# Power.net
KiCad netlist of a schematic drawn in Altium Designer
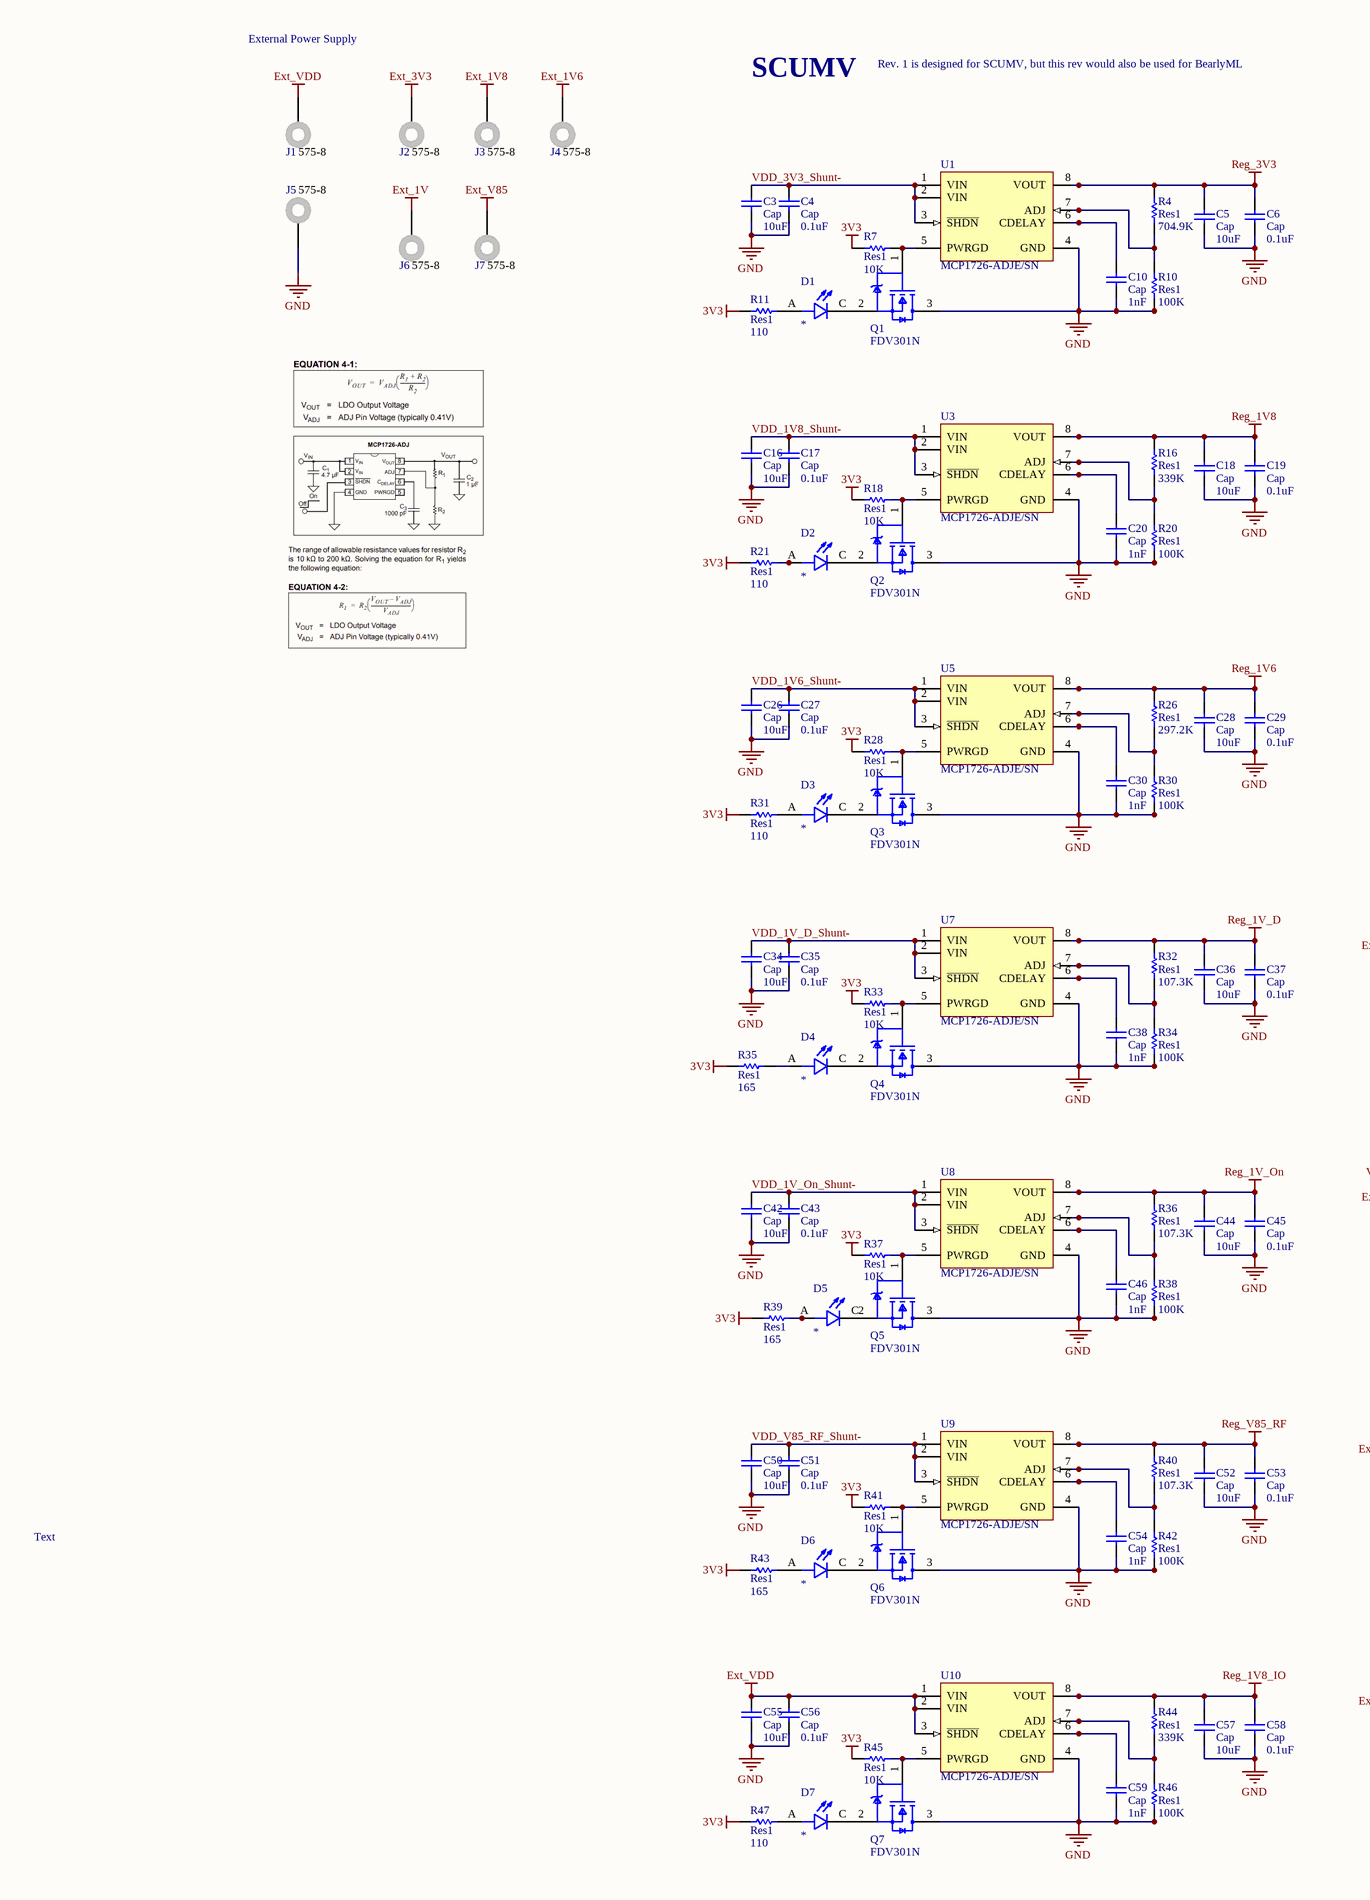
[diagram p0: Power.SchDoc, left]
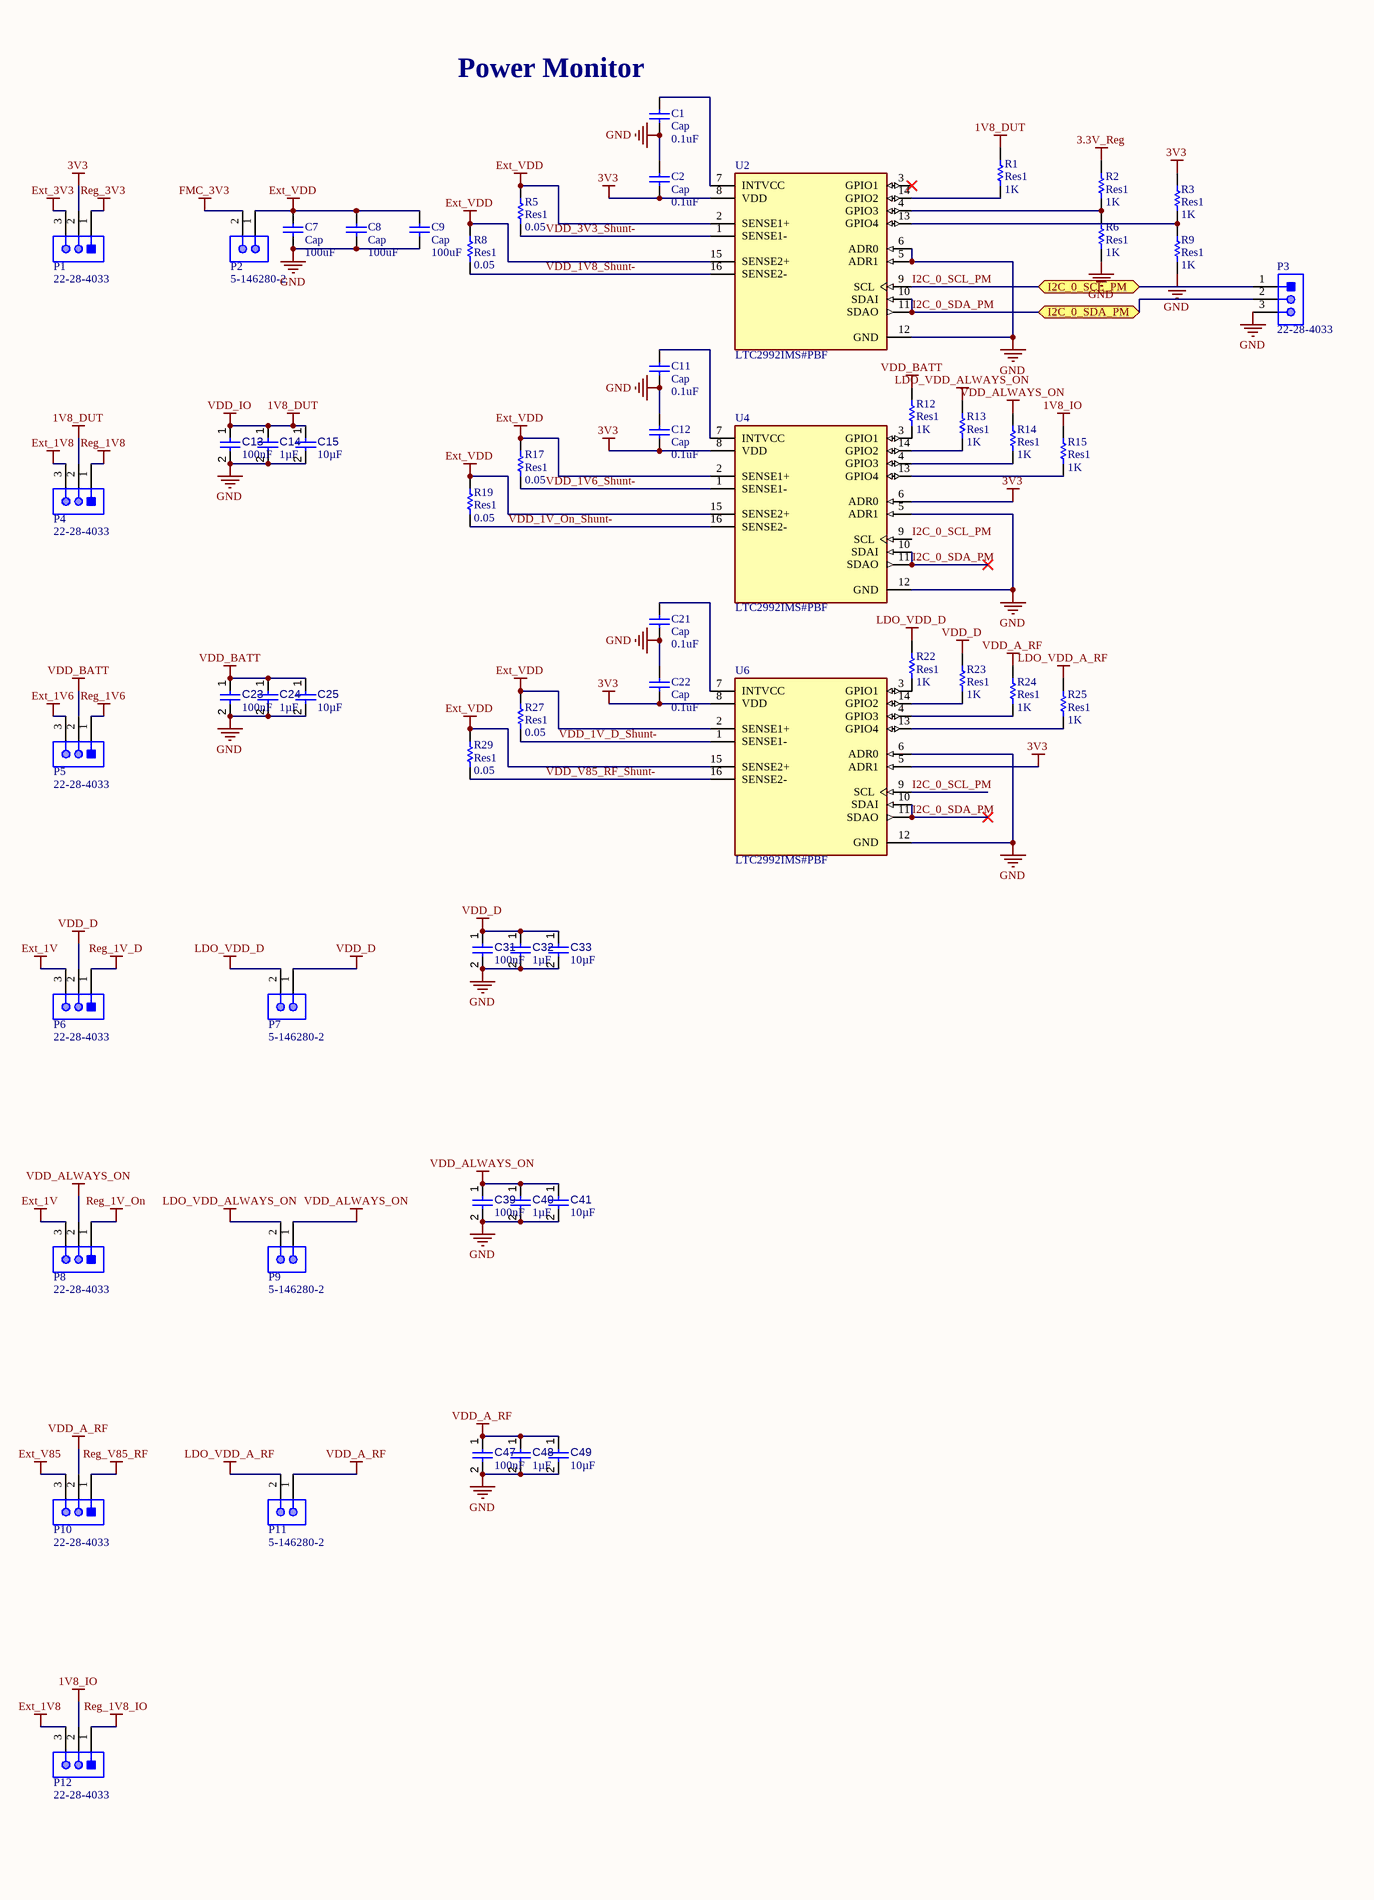
[diagram p1: Power.SchDoc, right]

(export (version "E")
  (design (tool "Eeschema 10.0.6"))
  (components
    (comp (ref "C1")
      (value "Cap")
      (footprint "0603")
      (description "Capacitor")
      (fields (field (name "ALTIUM_VALUE") "0.1uF") (field (name "PUBLISHER") "Altium Limited"))
      (libsource (lib "Miscellaneous Devices") (part "Cap"))
    )
    (comp (ref "C2")
      (value "Cap")
      (footprint "0603")
      (description "Capacitor")
      (fields (field (name "ALTIUM_VALUE") "0.1uF") (field (name "PUBLISHER") "Altium Limited"))
      (libsource (lib "Miscellaneous Devices") (part "Cap"))
    )
    (comp (ref "C3")
      (value "Cap")
      (footprint "0805")
      (description "Capacitor")
      (fields (field (name "ALTIUM_VALUE") "10uF") (field (name "PUBLISHER") "Altium Limited"))
      (libsource (lib "Miscellaneous Devices") (part "Cap"))
    )
    (comp (ref "C4")
      (value "Cap")
      (footprint "0603")
      (description "Capacitor")
      (fields (field (name "ALTIUM_VALUE") "0.1uF") (field (name "PUBLISHER") "Altium Limited"))
      (libsource (lib "Miscellaneous Devices") (part "Cap"))
    )
    (comp (ref "C5")
      (value "Cap")
      (footprint "0805")
      (description "Capacitor")
      (fields (field (name "ALTIUM_VALUE") "10uF") (field (name "PUBLISHER") "Altium Limited"))
      (libsource (lib "Miscellaneous Devices") (part "Cap"))
    )
    (comp (ref "C6")
      (value "Cap")
      (footprint "0603")
      (description "Capacitor")
      (fields (field (name "ALTIUM_VALUE") "0.1uF") (field (name "PUBLISHER") "Altium Limited"))
      (libsource (lib "Miscellaneous Devices") (part "Cap"))
    )
    (comp (ref "C7")
      (value "Cap")
      (footprint "0805")
      (description "Capacitor")
      (fields (field (name "ALTIUM_VALUE") "100uF") (field (name "PUBLISHER") "Altium Limited"))
      (libsource (lib "Miscellaneous Devices") (part "Cap"))
    )
    (comp (ref "C8")
      (value "Cap")
      (footprint "0805")
      (description "Capacitor")
      (fields (field (name "ALTIUM_VALUE") "100uF") (field (name "PUBLISHER") "Altium Limited"))
      (libsource (lib "Miscellaneous Devices") (part "Cap"))
    )
    (comp (ref "C9")
      (value "Cap")
      (footprint "0805")
      (description "Capacitor")
      (fields (field (name "ALTIUM_VALUE") "100uF") (field (name "PUBLISHER") "Altium Limited"))
      (libsource (lib "Miscellaneous Devices") (part "Cap"))
    )
    (comp (ref "C10")
      (value "Cap")
      (footprint "0603")
      (description "Capacitor")
      (fields (field (name "ALTIUM_VALUE") "1nF") (field (name "PUBLISHER") "Altium Limited"))
      (libsource (lib "Miscellaneous Devices") (part "Cap"))
    )
    (comp (ref "C11")
      (value "Cap")
      (footprint "0603")
      (description "Capacitor")
      (fields (field (name "ALTIUM_VALUE") "0.1uF") (field (name "PUBLISHER") "Altium Limited"))
      (libsource (lib "Miscellaneous Devices") (part "Cap"))
    )
    (comp (ref "C12")
      (value "Cap")
      (footprint "0603")
      (description "Capacitor")
      (fields (field (name "ALTIUM_VALUE") "0.1uF") (field (name "PUBLISHER") "Altium Limited"))
      (libsource (lib "Miscellaneous Devices") (part "Cap"))
    )
    (comp (ref "C13")
      (value "100nF")
      (footprint "CAPC0402(1005)60_L")
      (description "Chip Capacitor, 100nF +/-20%, 10V, 0402, Thickness 0.6 mm")
      (fields (field (name "TOLERANCE") "20%") (field (name "Comment") "Capacitor 100nF +/-20% 10V 0402"))
      (libsource (lib "EE194 Fall2022") (part "CAP-NP-2"))
    )
    (comp (ref "C14")
      (value "1µF")
      (footprint "CAPC0402(1005)60_L")
      (description "Chip Capacitor, 1µF +/-20%, 10V, 0402, Thickness 0.6 mm")
      (fields (field (name "TOLERANCE") "10%") (field (name "Comment") "Capacitor 1µF +/-20% 10V 0402"))
      (libsource (lib "EE194 Fall2022") (part "CAP-NP-2"))
    )
    (comp (ref "C15")
      (value "10µF")
      (footprint "CAPC0402(1005)60_L")
      (description "Chip Capacitor, 10µF +/-40%, 6.3V, 0402, Thickness 0.6 mm")
      (fields (field (name "TOLERANCE") "10%") (field (name "Comment") "Capacitor 10µF +/-40% 6.3V 0402"))
      (libsource (lib "EE194 Fall2022") (part "CAP-NP-2"))
    )
    (comp (ref "C16")
      (value "Cap")
      (footprint "0805")
      (description "Capacitor")
      (fields (field (name "ALTIUM_VALUE") "10uF") (field (name "PUBLISHER") "Altium Limited"))
      (libsource (lib "Miscellaneous Devices") (part "Cap"))
    )
    (comp (ref "C17")
      (value "Cap")
      (footprint "0603")
      (description "Capacitor")
      (fields (field (name "ALTIUM_VALUE") "0.1uF") (field (name "PUBLISHER") "Altium Limited"))
      (libsource (lib "Miscellaneous Devices") (part "Cap"))
    )
    (comp (ref "C18")
      (value "Cap")
      (footprint "0805")
      (description "Capacitor")
      (fields (field (name "ALTIUM_VALUE") "10uF") (field (name "PUBLISHER") "Altium Limited"))
      (libsource (lib "Miscellaneous Devices") (part "Cap"))
    )
    (comp (ref "C19")
      (value "Cap")
      (footprint "0603")
      (description "Capacitor")
      (fields (field (name "ALTIUM_VALUE") "0.1uF") (field (name "PUBLISHER") "Altium Limited"))
      (libsource (lib "Miscellaneous Devices") (part "Cap"))
    )
    (comp (ref "C20")
      (value "Cap")
      (footprint "0603")
      (description "Capacitor")
      (fields (field (name "ALTIUM_VALUE") "1nF") (field (name "PUBLISHER") "Altium Limited"))
      (libsource (lib "Miscellaneous Devices") (part "Cap"))
    )
    (comp (ref "C21")
      (value "Cap")
      (footprint "0603")
      (description "Capacitor")
      (fields (field (name "ALTIUM_VALUE") "0.1uF") (field (name "PUBLISHER") "Altium Limited"))
      (libsource (lib "Miscellaneous Devices") (part "Cap"))
    )
    (comp (ref "C22")
      (value "Cap")
      (footprint "0603")
      (description "Capacitor")
      (fields (field (name "ALTIUM_VALUE") "0.1uF") (field (name "PUBLISHER") "Altium Limited"))
      (libsource (lib "Miscellaneous Devices") (part "Cap"))
    )
    (comp (ref "C23")
      (value "100nF")
      (footprint "CAPC0402(1005)60_L")
      (description "Chip Capacitor, 100nF +/-20%, 10V, 0402, Thickness 0.6 mm")
      (fields (field (name "TOLERANCE") "20%") (field (name "Comment") "Capacitor 100nF +/-20% 10V 0402"))
      (libsource (lib "EE194 Fall2022") (part "CAP-NP-2"))
    )
    (comp (ref "C24")
      (value "1µF")
      (footprint "CAPC0402(1005)60_L")
      (description "Chip Capacitor, 1µF +/-20%, 10V, 0402, Thickness 0.6 mm")
      (fields (field (name "TOLERANCE") "10%") (field (name "Comment") "Capacitor 1µF +/-20% 10V 0402"))
      (libsource (lib "EE194 Fall2022") (part "CAP-NP-2"))
    )
    (comp (ref "C25")
      (value "10µF")
      (footprint "CAPC0402(1005)60_L")
      (description "Chip Capacitor, 10µF +/-40%, 6.3V, 0402, Thickness 0.6 mm")
      (fields (field (name "TOLERANCE") "10%") (field (name "Comment") "Capacitor 10µF +/-40% 6.3V 0402"))
      (libsource (lib "EE194 Fall2022") (part "CAP-NP-2"))
    )
    (comp (ref "C26")
      (value "Cap")
      (footprint "0805")
      (description "Capacitor")
      (fields (field (name "ALTIUM_VALUE") "10uF") (field (name "PUBLISHER") "Altium Limited"))
      (libsource (lib "Miscellaneous Devices") (part "Cap"))
    )
    (comp (ref "C27")
      (value "Cap")
      (footprint "0603")
      (description "Capacitor")
      (fields (field (name "ALTIUM_VALUE") "0.1uF") (field (name "PUBLISHER") "Altium Limited"))
      (libsource (lib "Miscellaneous Devices") (part "Cap"))
    )
    (comp (ref "C28")
      (value "Cap")
      (footprint "0805")
      (description "Capacitor")
      (fields (field (name "ALTIUM_VALUE") "10uF") (field (name "PUBLISHER") "Altium Limited"))
      (libsource (lib "Miscellaneous Devices") (part "Cap"))
    )
    (comp (ref "C29")
      (value "Cap")
      (footprint "0603")
      (description "Capacitor")
      (fields (field (name "ALTIUM_VALUE") "0.1uF") (field (name "PUBLISHER") "Altium Limited"))
      (libsource (lib "Miscellaneous Devices") (part "Cap"))
    )
    (comp (ref "C30")
      (value "Cap")
      (footprint "0603")
      (description "Capacitor")
      (fields (field (name "ALTIUM_VALUE") "1nF") (field (name "PUBLISHER") "Altium Limited"))
      (libsource (lib "Miscellaneous Devices") (part "Cap"))
    )
    (comp (ref "C31")
      (value "100nF")
      (footprint "CAPC0402(1005)60_L")
      (description "Chip Capacitor, 100nF +/-20%, 10V, 0402, Thickness 0.6 mm")
      (fields (field (name "TOLERANCE") "20%") (field (name "Comment") "Capacitor 100nF +/-20% 10V 0402"))
      (libsource (lib "EE194 Fall2022") (part "CAP-NP-2"))
    )
    (comp (ref "C32")
      (value "1µF")
      (footprint "CAPC0402(1005)60_L")
      (description "Chip Capacitor, 1µF +/-20%, 10V, 0402, Thickness 0.6 mm")
      (fields (field (name "TOLERANCE") "10%") (field (name "Comment") "Capacitor 1µF +/-20% 10V 0402"))
      (libsource (lib "EE194 Fall2022") (part "CAP-NP-2"))
    )
    (comp (ref "C33")
      (value "10µF")
      (footprint "CAPC0402(1005)60_L")
      (description "Chip Capacitor, 10µF +/-40%, 6.3V, 0402, Thickness 0.6 mm")
      (fields (field (name "TOLERANCE") "10%") (field (name "Comment") "Capacitor 10µF +/-40% 6.3V 0402"))
      (libsource (lib "EE194 Fall2022") (part "CAP-NP-2"))
    )
    (comp (ref "C34")
      (value "Cap")
      (footprint "0805")
      (description "Capacitor")
      (fields (field (name "ALTIUM_VALUE") "10uF") (field (name "PUBLISHER") "Altium Limited"))
      (libsource (lib "Miscellaneous Devices") (part "Cap"))
    )
    (comp (ref "C35")
      (value "Cap")
      (footprint "0603")
      (description "Capacitor")
      (fields (field (name "ALTIUM_VALUE") "0.1uF") (field (name "PUBLISHER") "Altium Limited"))
      (libsource (lib "Miscellaneous Devices") (part "Cap"))
    )
    (comp (ref "C36")
      (value "Cap")
      (footprint "0805")
      (description "Capacitor")
      (fields (field (name "ALTIUM_VALUE") "10uF") (field (name "PUBLISHER") "Altium Limited"))
      (libsource (lib "Miscellaneous Devices") (part "Cap"))
    )
    (comp (ref "C37")
      (value "Cap")
      (footprint "0603")
      (description "Capacitor")
      (fields (field (name "ALTIUM_VALUE") "0.1uF") (field (name "PUBLISHER") "Altium Limited"))
      (libsource (lib "Miscellaneous Devices") (part "Cap"))
    )
    (comp (ref "C38")
      (value "Cap")
      (footprint "0603")
      (description "Capacitor")
      (fields (field (name "ALTIUM_VALUE") "1nF") (field (name "PUBLISHER") "Altium Limited"))
      (libsource (lib "Miscellaneous Devices") (part "Cap"))
    )
    (comp (ref "C39")
      (value "100nF")
      (footprint "CAPC0402(1005)60_L")
      (description "Chip Capacitor, 100nF +/-20%, 10V, 0402, Thickness 0.6 mm")
      (fields (field (name "TOLERANCE") "20%") (field (name "Comment") "Capacitor 100nF +/-20% 10V 0402"))
      (libsource (lib "EE194 Fall2022") (part "CAP-NP-2"))
    )
    (comp (ref "C40")
      (value "1µF")
      (footprint "CAPC0402(1005)60_L")
      (description "Chip Capacitor, 1µF +/-20%, 10V, 0402, Thickness 0.6 mm")
      (fields (field (name "TOLERANCE") "10%") (field (name "Comment") "Capacitor 1µF +/-20% 10V 0402"))
      (libsource (lib "EE194 Fall2022") (part "CAP-NP-2"))
    )
    (comp (ref "C41")
      (value "10µF")
      (footprint "CAPC0402(1005)60_L")
      (description "Chip Capacitor, 10µF +/-40%, 6.3V, 0402, Thickness 0.6 mm")
      (fields (field (name "TOLERANCE") "10%") (field (name "Comment") "Capacitor 10µF +/-40% 6.3V 0402"))
      (libsource (lib "EE194 Fall2022") (part "CAP-NP-2"))
    )
    (comp (ref "C42")
      (value "Cap")
      (footprint "0805")
      (description "Capacitor")
      (fields (field (name "ALTIUM_VALUE") "10uF") (field (name "PUBLISHER") "Altium Limited"))
      (libsource (lib "Miscellaneous Devices") (part "Cap"))
    )
    (comp (ref "C43")
      (value "Cap")
      (footprint "0603")
      (description "Capacitor")
      (fields (field (name "ALTIUM_VALUE") "0.1uF") (field (name "PUBLISHER") "Altium Limited"))
      (libsource (lib "Miscellaneous Devices") (part "Cap"))
    )
    (comp (ref "C44")
      (value "Cap")
      (footprint "0805")
      (description "Capacitor")
      (fields (field (name "ALTIUM_VALUE") "10uF") (field (name "PUBLISHER") "Altium Limited"))
      (libsource (lib "Miscellaneous Devices") (part "Cap"))
    )
    (comp (ref "C45")
      (value "Cap")
      (footprint "0603")
      (description "Capacitor")
      (fields (field (name "ALTIUM_VALUE") "0.1uF") (field (name "PUBLISHER") "Altium Limited"))
      (libsource (lib "Miscellaneous Devices") (part "Cap"))
    )
    (comp (ref "C46")
      (value "Cap")
      (footprint "0603")
      (description "Capacitor")
      (fields (field (name "ALTIUM_VALUE") "1nF") (field (name "PUBLISHER") "Altium Limited"))
      (libsource (lib "Miscellaneous Devices") (part "Cap"))
    )
    (comp (ref "C47")
      (value "100nF")
      (footprint "CAPC0402(1005)60_L")
      (description "Chip Capacitor, 100nF +/-20%, 10V, 0402, Thickness 0.6 mm")
      (fields (field (name "TOLERANCE") "20%") (field (name "Comment") "Capacitor 100nF +/-20% 10V 0402"))
      (libsource (lib "EE194 Fall2022") (part "CAP-NP-2"))
    )
    (comp (ref "C48")
      (value "1µF")
      (footprint "CAPC0402(1005)60_L")
      (description "Chip Capacitor, 1µF +/-20%, 10V, 0402, Thickness 0.6 mm")
      (fields (field (name "TOLERANCE") "10%") (field (name "Comment") "Capacitor 1µF +/-20% 10V 0402"))
      (libsource (lib "EE194 Fall2022") (part "CAP-NP-2"))
    )
    (comp (ref "C49")
      (value "10µF")
      (footprint "CAPC0402(1005)60_L")
      (description "Chip Capacitor, 10µF +/-40%, 6.3V, 0402, Thickness 0.6 mm")
      (fields (field (name "TOLERANCE") "10%") (field (name "Comment") "Capacitor 10µF +/-40% 6.3V 0402"))
      (libsource (lib "EE194 Fall2022") (part "CAP-NP-2"))
    )
    (comp (ref "C50")
      (value "Cap")
      (footprint "0805")
      (description "Capacitor")
      (fields (field (name "ALTIUM_VALUE") "10uF") (field (name "PUBLISHER") "Altium Limited"))
      (libsource (lib "Miscellaneous Devices") (part "Cap"))
    )
    (comp (ref "C51")
      (value "Cap")
      (footprint "0603")
      (description "Capacitor")
      (fields (field (name "ALTIUM_VALUE") "0.1uF") (field (name "PUBLISHER") "Altium Limited"))
      (libsource (lib "Miscellaneous Devices") (part "Cap"))
    )
    (comp (ref "C52")
      (value "Cap")
      (footprint "0805")
      (description "Capacitor")
      (fields (field (name "ALTIUM_VALUE") "10uF") (field (name "PUBLISHER") "Altium Limited"))
      (libsource (lib "Miscellaneous Devices") (part "Cap"))
    )
    (comp (ref "C53")
      (value "Cap")
      (footprint "0603")
      (description "Capacitor")
      (fields (field (name "ALTIUM_VALUE") "0.1uF") (field (name "PUBLISHER") "Altium Limited"))
      (libsource (lib "Miscellaneous Devices") (part "Cap"))
    )
    (comp (ref "C54")
      (value "Cap")
      (footprint "0603")
      (description "Capacitor")
      (fields (field (name "ALTIUM_VALUE") "1nF") (field (name "PUBLISHER") "Altium Limited"))
      (libsource (lib "Miscellaneous Devices") (part "Cap"))
    )
    (comp (ref "C55")
      (value "Cap")
      (footprint "0805")
      (description "Capacitor")
      (fields (field (name "ALTIUM_VALUE") "10uF") (field (name "PUBLISHER") "Altium Limited"))
      (libsource (lib "Miscellaneous Devices") (part "Cap"))
    )
    (comp (ref "C56")
      (value "Cap")
      (footprint "0603")
      (description "Capacitor")
      (fields (field (name "ALTIUM_VALUE") "0.1uF") (field (name "PUBLISHER") "Altium Limited"))
      (libsource (lib "Miscellaneous Devices") (part "Cap"))
    )
    (comp (ref "C57")
      (value "Cap")
      (footprint "0805")
      (description "Capacitor")
      (fields (field (name "ALTIUM_VALUE") "10uF") (field (name "PUBLISHER") "Altium Limited"))
      (libsource (lib "Miscellaneous Devices") (part "Cap"))
    )
    (comp (ref "C58")
      (value "Cap")
      (footprint "0603")
      (description "Capacitor")
      (fields (field (name "ALTIUM_VALUE") "0.1uF") (field (name "PUBLISHER") "Altium Limited"))
      (libsource (lib "Miscellaneous Devices") (part "Cap"))
    )
    (comp (ref "C59")
      (value "Cap")
      (footprint "0603")
      (description "Capacitor")
      (fields (field (name "ALTIUM_VALUE") "1nF") (field (name "PUBLISHER") "Altium Limited"))
      (libsource (lib "Miscellaneous Devices") (part "Cap"))
    )
    (comp (ref "D1")
      (value "LTW-C191DS5")
      (footprint "LED0603")
      (description "White LED Indication - Discrete 2.93V 0603 _1608 Metric_")
      (fields (field (name "MF") "Lite-On Inc.") (field (name "ALTIUM_VALUE") "*"))
      (libsource (lib "EE194 Fall2022") (part "LTW-C191DS5"))
    )
    (comp (ref "D2")
      (value "LTW-C191DS5")
      (footprint "LED0603")
      (description "White LED Indication - Discrete 2.93V 0603 _1608 Metric_")
      (fields (field (name "MF") "Lite-On Inc.") (field (name "ALTIUM_VALUE") "*"))
      (libsource (lib "EE194 Fall2022") (part "LTW-C191DS5"))
    )
    (comp (ref "D3")
      (value "LTW-C191DS5")
      (footprint "LED0603")
      (description "White LED Indication - Discrete 2.93V 0603 _1608 Metric_")
      (fields (field (name "MF") "Lite-On Inc.") (field (name "ALTIUM_VALUE") "*"))
      (libsource (lib "EE194 Fall2022") (part "LTW-C191DS5"))
    )
    (comp (ref "D4")
      (value "LTW-C191DS5")
      (footprint "LED0603")
      (description "White LED Indication - Discrete 2.93V 0603 _1608 Metric_")
      (fields (field (name "MF") "Lite-On Inc.") (field (name "ALTIUM_VALUE") "*"))
      (libsource (lib "EE194 Fall2022") (part "LTW-C191DS5"))
    )
    (comp (ref "D5")
      (value "LTW-C191DS5")
      (footprint "LED0603")
      (description "White LED Indication - Discrete 2.93V 0603 _1608 Metric_")
      (fields (field (name "MF") "Lite-On Inc.") (field (name "ALTIUM_VALUE") "*"))
      (libsource (lib "EE194 Fall2022") (part "LTW-C191DS5"))
    )
    (comp (ref "D6")
      (value "LTW-C191DS5")
      (footprint "LED0603")
      (description "White LED Indication - Discrete 2.93V 0603 _1608 Metric_")
      (fields (field (name "MF") "Lite-On Inc.") (field (name "ALTIUM_VALUE") "*"))
      (libsource (lib "EE194 Fall2022") (part "LTW-C191DS5"))
    )
    (comp (ref "D7")
      (value "LTW-C191DS5")
      (footprint "LED0603")
      (description "White LED Indication - Discrete 2.93V 0603 _1608 Metric_")
      (fields (field (name "MF") "Lite-On Inc.") (field (name "ALTIUM_VALUE") "*"))
      (libsource (lib "EE194 Fall2022") (part "LTW-C191DS5"))
    )
    (comp (ref "J1")
      (value "575-8")
      (footprint "KSTN-575-8")
      (description "Non-Insulated Jack, Through Hole, RoHS, Bulk")
      (fields (field (name "MANUFACTURER") "Keystone"))
      (libsource (lib "Altium Content Vault") (part "KSTN-575-8"))
    )
    (comp (ref "J2")
      (value "575-8")
      (footprint "KSTN-575-8")
      (description "Non-Insulated Jack, Through Hole, RoHS, Bulk")
      (fields (field (name "MANUFACTURER") "Keystone"))
      (libsource (lib "Altium Content Vault") (part "KSTN-575-8"))
    )
    (comp (ref "J3")
      (value "575-8")
      (footprint "KSTN-575-8")
      (description "Non-Insulated Jack, Through Hole, RoHS, Bulk")
      (fields (field (name "MANUFACTURER") "Keystone"))
      (libsource (lib "Altium Content Vault") (part "KSTN-575-8"))
    )
    (comp (ref "J4")
      (value "575-8")
      (footprint "KSTN-575-8")
      (description "Non-Insulated Jack, Through Hole, RoHS, Bulk")
      (fields (field (name "MANUFACTURER") "Keystone"))
      (libsource (lib "Altium Content Vault") (part "KSTN-575-8"))
    )
    (comp (ref "J5")
      (value "575-8")
      (footprint "KSTN-575-8")
      (description "Non-Insulated Jack, Through Hole, RoHS, Bulk")
      (fields (field (name "MANUFACTURER") "Keystone"))
      (libsource (lib "Altium Content Vault") (part "KSTN-575-8"))
    )
    (comp (ref "J6")
      (value "575-8")
      (footprint "KSTN-575-8")
      (description "Non-Insulated Jack, Through Hole, RoHS, Bulk")
      (fields (field (name "MANUFACTURER") "Keystone"))
      (libsource (lib "Altium Content Vault") (part "KSTN-575-8"))
    )
    (comp (ref "J7")
      (value "575-8")
      (footprint "KSTN-575-8")
      (description "Non-Insulated Jack, Through Hole, RoHS, Bulk")
      (fields (field (name "MANUFACTURER") "Keystone"))
      (libsource (lib "Altium Content Vault") (part "KSTN-575-8"))
    )
    (comp (ref "P1")
      (value "22-28-4033")
      (footprint "MOLX-22-28-4033_V")
      (description "Male Header, Pitch 2.54 mm, 1 x 3 Position, Height 8.38 mm, Tail Length 3.18 mm, RoHS, Bulk")
      (fields (field (name "MANUFACTURER") "Molex"))
      (libsource (lib "Altium Content Vault") (part "CN-1P-M-R3"))
    )
    (comp (ref "P2")
      (value "5-146280-2")
      (footprint "TECO-5-146280-2_V")
      (fields (field (name "MANUFACTURER") "TE Connectivity"))
      (libsource (lib "Altium Content Vault") (part "CN-1P-M-R2"))
    )
    (comp (ref "P3")
      (value "22-28-4033")
      (footprint "MOLX-22-28-4033_V")
      (description "Male Header, Pitch 2.54 mm, 1 x 3 Position, Height 8.38 mm, Tail Length 3.18 mm, RoHS, Bulk")
      (fields (field (name "MANUFACTURER") "Molex"))
      (libsource (lib "") (part "CN-1P-M-R3_1"))
    )
    (comp (ref "P4")
      (value "22-28-4033")
      (footprint "MOLX-22-28-4033_V")
      (description "Male Header, Pitch 2.54 mm, 1 x 3 Position, Height 8.38 mm, Tail Length 3.18 mm, RoHS, Bulk")
      (fields (field (name "MANUFACTURER") "Molex"))
      (libsource (lib "Altium Content Vault") (part "CN-1P-M-R3"))
    )
    (comp (ref "P5")
      (value "22-28-4033")
      (footprint "MOLX-22-28-4033_V")
      (description "Male Header, Pitch 2.54 mm, 1 x 3 Position, Height 8.38 mm, Tail Length 3.18 mm, RoHS, Bulk")
      (fields (field (name "MANUFACTURER") "Molex"))
      (libsource (lib "Altium Content Vault") (part "CN-1P-M-R3"))
    )
    (comp (ref "P6")
      (value "22-28-4033")
      (footprint "MOLX-22-28-4033_V")
      (description "Male Header, Pitch 2.54 mm, 1 x 3 Position, Height 8.38 mm, Tail Length 3.18 mm, RoHS, Bulk")
      (fields (field (name "MANUFACTURER") "Molex"))
      (libsource (lib "Altium Content Vault") (part "CN-1P-M-R3"))
    )
    (comp (ref "P7")
      (value "5-146280-2")
      (footprint "TECO-5-146280-2_V")
      (fields (field (name "MANUFACTURER") "TE Connectivity"))
      (libsource (lib "Altium Content Vault") (part "CN-1P-M-R2"))
    )
    (comp (ref "P8")
      (value "22-28-4033")
      (footprint "MOLX-22-28-4033_V")
      (description "Male Header, Pitch 2.54 mm, 1 x 3 Position, Height 8.38 mm, Tail Length 3.18 mm, RoHS, Bulk")
      (fields (field (name "MANUFACTURER") "Molex"))
      (libsource (lib "Altium Content Vault") (part "CN-1P-M-R3"))
    )
    (comp (ref "P9")
      (value "5-146280-2")
      (footprint "TECO-5-146280-2_V")
      (fields (field (name "MANUFACTURER") "TE Connectivity"))
      (libsource (lib "Altium Content Vault") (part "CN-1P-M-R2"))
    )
    (comp (ref "P10")
      (value "22-28-4033")
      (footprint "MOLX-22-28-4033_V")
      (description "Male Header, Pitch 2.54 mm, 1 x 3 Position, Height 8.38 mm, Tail Length 3.18 mm, RoHS, Bulk")
      (fields (field (name "MANUFACTURER") "Molex"))
      (libsource (lib "Altium Content Vault") (part "CN-1P-M-R3"))
    )
    (comp (ref "P11")
      (value "5-146280-2")
      (footprint "TECO-5-146280-2_V")
      (fields (field (name "MANUFACTURER") "TE Connectivity"))
      (libsource (lib "Altium Content Vault") (part "CN-1P-M-R2"))
    )
    (comp (ref "P12")
      (value "22-28-4033")
      (footprint "MOLX-22-28-4033_V")
      (description "Male Header, Pitch 2.54 mm, 1 x 3 Position, Height 8.38 mm, Tail Length 3.18 mm, RoHS, Bulk")
      (fields (field (name "MANUFACTURER") "Molex"))
      (libsource (lib "Altium Content Vault") (part "CN-1P-M-R3"))
    )
    (comp (ref "Q1")
      (value "FDV301N")
      (footprint "FP-318-08-MFG")
      (description "MOSFET N-CH 25V 220MA SOT-23")
      (fields
        (field (name "MANUFACTURER") "ON Semiconductor")
        (field (name "OCTOPART") "https://octopart.com/fdv301n-on+semiconductor-84326713")
      )
      (libsource (lib "Altium Content Vault") (part "4b65c62267dd4506eaef0021093ec31"))
    )
    (comp (ref "Q2")
      (value "FDV301N")
      (footprint "FP-318-08-MFG")
      (description "MOSFET N-CH 25V 220MA SOT-23")
      (fields
        (field (name "MANUFACTURER") "ON Semiconductor")
        (field (name "OCTOPART") "https://octopart.com/fdv301n-on+semiconductor-84326713")
      )
      (libsource (lib "Altium Content Vault") (part "4b65c62267dd4506eaef0021093ec31"))
    )
    (comp (ref "Q3")
      (value "FDV301N")
      (footprint "FP-318-08-MFG")
      (description "MOSFET N-CH 25V 220MA SOT-23")
      (fields
        (field (name "MANUFACTURER") "ON Semiconductor")
        (field (name "OCTOPART") "https://octopart.com/fdv301n-on+semiconductor-84326713")
      )
      (libsource (lib "Altium Content Vault") (part "4b65c62267dd4506eaef0021093ec31"))
    )
    (comp (ref "Q4")
      (value "FDV301N")
      (footprint "FP-318-08-MFG")
      (description "MOSFET N-CH 25V 220MA SOT-23")
      (fields
        (field (name "MANUFACTURER") "ON Semiconductor")
        (field (name "OCTOPART") "https://octopart.com/fdv301n-on+semiconductor-84326713")
      )
      (libsource (lib "Altium Content Vault") (part "4b65c62267dd4506eaef0021093ec31"))
    )
    (comp (ref "Q5")
      (value "FDV301N")
      (footprint "FP-318-08-MFG")
      (description "MOSFET N-CH 25V 220MA SOT-23")
      (fields
        (field (name "MANUFACTURER") "ON Semiconductor")
        (field (name "OCTOPART") "https://octopart.com/fdv301n-on+semiconductor-84326713")
      )
      (libsource (lib "Altium Content Vault") (part "4b65c62267dd4506eaef0021093ec31"))
    )
    (comp (ref "Q6")
      (value "FDV301N")
      (footprint "FP-318-08-MFG")
      (description "MOSFET N-CH 25V 220MA SOT-23")
      (fields
        (field (name "MANUFACTURER") "ON Semiconductor")
        (field (name "OCTOPART") "https://octopart.com/fdv301n-on+semiconductor-84326713")
      )
      (libsource (lib "Altium Content Vault") (part "4b65c62267dd4506eaef0021093ec31"))
    )
    (comp (ref "Q7")
      (value "FDV301N")
      (footprint "FP-318-08-MFG")
      (description "MOSFET N-CH 25V 220MA SOT-23")
      (fields
        (field (name "MANUFACTURER") "ON Semiconductor")
        (field (name "OCTOPART") "https://octopart.com/fdv301n-on+semiconductor-84326713")
      )
      (libsource (lib "Altium Content Vault") (part "4b65c62267dd4506eaef0021093ec31"))
    )
    (comp (ref "R1")
      (value "Res1")
      (footprint "0603")
      (description "Resistor")
      (fields (field (name "ALTIUM_VALUE") "1K") (field (name "PUBLISHER") "Altium Limited"))
      (libsource (lib "Miscellaneous Devices") (part "Res1"))
    )
    (comp (ref "R2")
      (value "Res1")
      (footprint "0603")
      (description "Resistor")
      (fields (field (name "ALTIUM_VALUE") "1K") (field (name "PUBLISHER") "Altium Limited"))
      (libsource (lib "Miscellaneous Devices") (part "Res1"))
    )
    (comp (ref "R3")
      (value "Res1")
      (footprint "0603")
      (description "Resistor")
      (fields (field (name "ALTIUM_VALUE") "1K") (field (name "PUBLISHER") "Altium Limited"))
      (libsource (lib "Miscellaneous Devices") (part "Res1"))
    )
    (comp (ref "R4")
      (value "Res1")
      (footprint "0603")
      (description "Resistor")
      (fields (field (name "ALTIUM_VALUE") "704.9K") (field (name "PUBLISHER") "Altium Limited"))
      (libsource (lib "Miscellaneous Devices") (part "Res1"))
    )
    (comp (ref "R5")
      (value "Res1")
      (footprint "0603")
      (description "Resistor")
      (fields (field (name "ALTIUM_VALUE") "0.05") (field (name "PUBLISHER") "Altium Limited"))
      (libsource (lib "Miscellaneous Devices") (part "Res1"))
    )
    (comp (ref "R6")
      (value "Res1")
      (footprint "0603")
      (description "Resistor")
      (fields (field (name "ALTIUM_VALUE") "1K") (field (name "PUBLISHER") "Altium Limited"))
      (libsource (lib "Miscellaneous Devices") (part "Res1"))
    )
    (comp (ref "R7")
      (value "Res1")
      (footprint "0603")
      (description "Resistor")
      (fields (field (name "ALTIUM_VALUE") "10K") (field (name "PUBLISHER") "Altium Limited"))
      (libsource (lib "Miscellaneous Devices") (part "Res1"))
    )
    (comp (ref "R8")
      (value "Res1")
      (footprint "0603")
      (description "Resistor")
      (fields (field (name "ALTIUM_VALUE") "0.05") (field (name "PUBLISHER") "Altium Limited"))
      (libsource (lib "Miscellaneous Devices") (part "Res1"))
    )
    (comp (ref "R9")
      (value "Res1")
      (footprint "0603")
      (description "Resistor")
      (fields (field (name "ALTIUM_VALUE") "1K") (field (name "PUBLISHER") "Altium Limited"))
      (libsource (lib "Miscellaneous Devices") (part "Res1"))
    )
    (comp (ref "R10")
      (value "Res1")
      (footprint "0603")
      (description "Resistor")
      (fields (field (name "ALTIUM_VALUE") "100K") (field (name "PUBLISHER") "Altium Limited"))
      (libsource (lib "Miscellaneous Devices") (part "Res1"))
    )
    (comp (ref "R11")
      (value "Res1")
      (footprint "0603")
      (description "Resistor")
      (fields (field (name "ALTIUM_VALUE") "110") (field (name "PUBLISHER") "Altium Limited"))
      (libsource (lib "Miscellaneous Devices") (part "Res1"))
    )
    (comp (ref "R12")
      (value "Res1")
      (footprint "0603")
      (description "Resistor")
      (fields (field (name "ALTIUM_VALUE") "1K") (field (name "PUBLISHER") "Altium Limited"))
      (libsource (lib "Miscellaneous Devices") (part "Res1"))
    )
    (comp (ref "R13")
      (value "Res1")
      (footprint "0603")
      (description "Resistor")
      (fields (field (name "ALTIUM_VALUE") "1K") (field (name "PUBLISHER") "Altium Limited"))
      (libsource (lib "Miscellaneous Devices") (part "Res1"))
    )
    (comp (ref "R14")
      (value "Res1")
      (footprint "0603")
      (description "Resistor")
      (fields (field (name "ALTIUM_VALUE") "1K") (field (name "PUBLISHER") "Altium Limited"))
      (libsource (lib "Miscellaneous Devices") (part "Res1"))
    )
    (comp (ref "R15")
      (value "Res1")
      (footprint "0603")
      (description "Resistor")
      (fields (field (name "ALTIUM_VALUE") "1K") (field (name "PUBLISHER") "Altium Limited"))
      (libsource (lib "Miscellaneous Devices") (part "Res1"))
    )
    (comp (ref "R16")
      (value "Res1")
      (footprint "0603")
      (description "Resistor")
      (fields (field (name "ALTIUM_VALUE") "339K") (field (name "PUBLISHER") "Altium Limited"))
      (libsource (lib "Miscellaneous Devices") (part "Res1"))
    )
    (comp (ref "R17")
      (value "Res1")
      (footprint "0603")
      (description "Resistor")
      (fields (field (name "ALTIUM_VALUE") "0.05") (field (name "PUBLISHER") "Altium Limited"))
      (libsource (lib "Miscellaneous Devices") (part "Res1"))
    )
    (comp (ref "R18")
      (value "Res1")
      (footprint "0603")
      (description "Resistor")
      (fields (field (name "ALTIUM_VALUE") "10K") (field (name "PUBLISHER") "Altium Limited"))
      (libsource (lib "Miscellaneous Devices") (part "Res1"))
    )
    (comp (ref "R19")
      (value "Res1")
      (footprint "0603")
      (description "Resistor")
      (fields (field (name "ALTIUM_VALUE") "0.05") (field (name "PUBLISHER") "Altium Limited"))
      (libsource (lib "Miscellaneous Devices") (part "Res1"))
    )
    (comp (ref "R20")
      (value "Res1")
      (footprint "0603")
      (description "Resistor")
      (fields (field (name "ALTIUM_VALUE") "100K") (field (name "PUBLISHER") "Altium Limited"))
      (libsource (lib "Miscellaneous Devices") (part "Res1"))
    )
    (comp (ref "R21")
      (value "Res1")
      (footprint "0603")
      (description "Resistor")
      (fields (field (name "ALTIUM_VALUE") "110") (field (name "PUBLISHER") "Altium Limited"))
      (libsource (lib "Miscellaneous Devices") (part "Res1"))
    )
    (comp (ref "R22")
      (value "Res1")
      (footprint "0603")
      (description "Resistor")
      (fields (field (name "ALTIUM_VALUE") "1K") (field (name "PUBLISHER") "Altium Limited"))
      (libsource (lib "Miscellaneous Devices") (part "Res1"))
    )
    (comp (ref "R23")
      (value "Res1")
      (footprint "0603")
      (description "Resistor")
      (fields (field (name "ALTIUM_VALUE") "1K") (field (name "PUBLISHER") "Altium Limited"))
      (libsource (lib "Miscellaneous Devices") (part "Res1"))
    )
    (comp (ref "R24")
      (value "Res1")
      (footprint "0603")
      (description "Resistor")
      (fields (field (name "ALTIUM_VALUE") "1K") (field (name "PUBLISHER") "Altium Limited"))
      (libsource (lib "Miscellaneous Devices") (part "Res1"))
    )
    (comp (ref "R25")
      (value "Res1")
      (footprint "0603")
      (description "Resistor")
      (fields (field (name "ALTIUM_VALUE") "1K") (field (name "PUBLISHER") "Altium Limited"))
      (libsource (lib "Miscellaneous Devices") (part "Res1"))
    )
    (comp (ref "R26")
      (value "Res1")
      (footprint "0603")
      (description "Resistor")
      (fields (field (name "ALTIUM_VALUE") "297.2K") (field (name "PUBLISHER") "Altium Limited"))
      (libsource (lib "Miscellaneous Devices") (part "Res1"))
    )
    (comp (ref "R27")
      (value "Res1")
      (footprint "0603")
      (description "Resistor")
      (fields (field (name "ALTIUM_VALUE") "0.05") (field (name "PUBLISHER") "Altium Limited"))
      (libsource (lib "Miscellaneous Devices") (part "Res1"))
    )
    (comp (ref "R28")
      (value "Res1")
      (footprint "0603")
      (description "Resistor")
      (fields (field (name "ALTIUM_VALUE") "10K") (field (name "PUBLISHER") "Altium Limited"))
      (libsource (lib "Miscellaneous Devices") (part "Res1"))
    )
    (comp (ref "R29")
      (value "Res1")
      (footprint "0603")
      (description "Resistor")
      (fields (field (name "ALTIUM_VALUE") "0.05") (field (name "PUBLISHER") "Altium Limited"))
      (libsource (lib "Miscellaneous Devices") (part "Res1"))
    )
    (comp (ref "R30")
      (value "Res1")
      (footprint "0603")
      (description "Resistor")
      (fields (field (name "ALTIUM_VALUE") "100K") (field (name "PUBLISHER") "Altium Limited"))
      (libsource (lib "Miscellaneous Devices") (part "Res1"))
    )
    (comp (ref "R31")
      (value "Res1")
      (footprint "0603")
      (description "Resistor")
      (fields (field (name "ALTIUM_VALUE") "110") (field (name "PUBLISHER") "Altium Limited"))
      (libsource (lib "Miscellaneous Devices") (part "Res1"))
    )
    (comp (ref "R32")
      (value "Res1")
      (footprint "0603")
      (description "Resistor")
      (fields (field (name "ALTIUM_VALUE") "107.3K") (field (name "PUBLISHER") "Altium Limited"))
      (libsource (lib "Miscellaneous Devices") (part "Res1"))
    )
    (comp (ref "R33")
      (value "Res1")
      (footprint "0603")
      (description "Resistor")
      (fields (field (name "ALTIUM_VALUE") "10K") (field (name "PUBLISHER") "Altium Limited"))
      (libsource (lib "Miscellaneous Devices") (part "Res1"))
    )
    (comp (ref "R34")
      (value "Res1")
      (footprint "0603")
      (description "Resistor")
      (fields (field (name "ALTIUM_VALUE") "100K") (field (name "PUBLISHER") "Altium Limited"))
      (libsource (lib "Miscellaneous Devices") (part "Res1"))
    )
    (comp (ref "R35")
      (value "Res1")
      (footprint "0603")
      (description "Resistor")
      (fields (field (name "ALTIUM_VALUE") "165") (field (name "PUBLISHER") "Altium Limited"))
      (libsource (lib "Miscellaneous Devices") (part "Res1"))
    )
    (comp (ref "R36")
      (value "Res1")
      (footprint "0603")
      (description "Resistor")
      (fields (field (name "ALTIUM_VALUE") "107.3K") (field (name "PUBLISHER") "Altium Limited"))
      (libsource (lib "Miscellaneous Devices") (part "Res1"))
    )
    (comp (ref "R37")
      (value "Res1")
      (footprint "0603")
      (description "Resistor")
      (fields (field (name "ALTIUM_VALUE") "10K") (field (name "PUBLISHER") "Altium Limited"))
      (libsource (lib "Miscellaneous Devices") (part "Res1"))
    )
    (comp (ref "R38")
      (value "Res1")
      (footprint "0603")
      (description "Resistor")
      (fields (field (name "ALTIUM_VALUE") "100K") (field (name "PUBLISHER") "Altium Limited"))
      (libsource (lib "Miscellaneous Devices") (part "Res1"))
    )
    (comp (ref "R39")
      (value "Res1")
      (footprint "0603")
      (description "Resistor")
      (fields (field (name "ALTIUM_VALUE") "165") (field (name "PUBLISHER") "Altium Limited"))
      (libsource (lib "Miscellaneous Devices") (part "Res1"))
    )
    (comp (ref "R40")
      (value "Res1")
      (footprint "0603")
      (description "Resistor")
      (fields (field (name "ALTIUM_VALUE") "107.3K") (field (name "PUBLISHER") "Altium Limited"))
      (libsource (lib "Miscellaneous Devices") (part "Res1"))
    )
    (comp (ref "R41")
      (value "Res1")
      (footprint "0603")
      (description "Resistor")
      (fields (field (name "ALTIUM_VALUE") "10K") (field (name "PUBLISHER") "Altium Limited"))
      (libsource (lib "Miscellaneous Devices") (part "Res1"))
    )
    (comp (ref "R42")
      (value "Res1")
      (footprint "0603")
      (description "Resistor")
      (fields (field (name "ALTIUM_VALUE") "100K") (field (name "PUBLISHER") "Altium Limited"))
      (libsource (lib "Miscellaneous Devices") (part "Res1"))
    )
    (comp (ref "R43")
      (value "Res1")
      (footprint "0603")
      (description "Resistor")
      (fields (field (name "ALTIUM_VALUE") "165") (field (name "PUBLISHER") "Altium Limited"))
      (libsource (lib "Miscellaneous Devices") (part "Res1"))
    )
    (comp (ref "R44")
      (value "Res1")
      (footprint "0603")
      (description "Resistor")
      (fields (field (name "ALTIUM_VALUE") "339K") (field (name "PUBLISHER") "Altium Limited"))
      (libsource (lib "Miscellaneous Devices") (part "Res1"))
    )
    (comp (ref "R45")
      (value "Res1")
      (footprint "0603")
      (description "Resistor")
      (fields (field (name "ALTIUM_VALUE") "10K") (field (name "PUBLISHER") "Altium Limited"))
      (libsource (lib "Miscellaneous Devices") (part "Res1"))
    )
    (comp (ref "R46")
      (value "Res1")
      (footprint "0603")
      (description "Resistor")
      (fields (field (name "ALTIUM_VALUE") "100K") (field (name "PUBLISHER") "Altium Limited"))
      (libsource (lib "Miscellaneous Devices") (part "Res1"))
    )
    (comp (ref "R47")
      (value "Res1")
      (footprint "0603")
      (description "Resistor")
      (fields (field (name "ALTIUM_VALUE") "110") (field (name "PUBLISHER") "Altium Limited"))
      (libsource (lib "Miscellaneous Devices") (part "Res1"))
    )
    (comp (ref "U1")
      (value "MCP1726-ADJE/SN")
      (footprint "SOIC-SN8_N")
      (description "1A, Low Voltage, Low Quiescent Current LDO Regulator, 8-Pin SOIC 150mil, Extended Temperature")
      (libsource (lib "Altium Content Vault") (part "PM-LINEREG-MCP1726-IL8A"))
    )
    (comp (ref "U2")
      (value "LTC2992IMS#PBF")
      (footprint "FP-MS-16-05-08-1669-IPC_C")
      (description "IC PWR MONITOR DUAL WIDE 16MSOP")
      (libsource (lib "Altium Content Vault") (part "5b94c4469b8b153b1e02272b3cbc136"))
    )
    (comp (ref "U3")
      (value "MCP1726-ADJE/SN")
      (footprint "SOIC-SN8_N")
      (description "1A, Low Voltage, Low Quiescent Current LDO Regulator, 8-Pin SOIC 150mil, Extended Temperature")
      (libsource (lib "Altium Content Vault") (part "PM-LINEREG-MCP1726-IL8A"))
    )
    (comp (ref "U4")
      (value "LTC2992IMS#PBF")
      (footprint "FP-MS-16-05-08-1669-IPC_C")
      (description "IC PWR MONITOR DUAL WIDE 16MSOP")
      (libsource (lib "Altium Content Vault") (part "5b94c4469b8b153b1e02272b3cbc136"))
    )
    (comp (ref "U5")
      (value "MCP1726-ADJE/SN")
      (footprint "SOIC-SN8_N")
      (description "1A, Low Voltage, Low Quiescent Current LDO Regulator, 8-Pin SOIC 150mil, Extended Temperature")
      (libsource (lib "Altium Content Vault") (part "PM-LINEREG-MCP1726-IL8A"))
    )
    (comp (ref "U6")
      (value "LTC2992IMS#PBF")
      (footprint "FP-MS-16-05-08-1669-IPC_C")
      (description "IC PWR MONITOR DUAL WIDE 16MSOP")
      (libsource (lib "Altium Content Vault") (part "5b94c4469b8b153b1e02272b3cbc136"))
    )
    (comp (ref "U7")
      (value "MCP1726-ADJE/SN")
      (footprint "SOIC-SN8_N")
      (description "1A, Low Voltage, Low Quiescent Current LDO Regulator, 8-Pin SOIC 150mil, Extended Temperature")
      (libsource (lib "Altium Content Vault") (part "PM-LINEREG-MCP1726-IL8A"))
    )
    (comp (ref "U8")
      (value "MCP1726-ADJE/SN")
      (footprint "SOIC-SN8_N")
      (description "1A, Low Voltage, Low Quiescent Current LDO Regulator, 8-Pin SOIC 150mil, Extended Temperature")
      (libsource (lib "Altium Content Vault") (part "PM-LINEREG-MCP1726-IL8A"))
    )
    (comp (ref "U9")
      (value "MCP1726-ADJE/SN")
      (footprint "SOIC-SN8_N")
      (description "1A, Low Voltage, Low Quiescent Current LDO Regulator, 8-Pin SOIC 150mil, Extended Temperature")
      (libsource (lib "Altium Content Vault") (part "PM-LINEREG-MCP1726-IL8A"))
    )
    (comp (ref "U10")
      (value "MCP1726-ADJE/SN")
      (footprint "SOIC-SN8_N")
      (description "1A, Low Voltage, Low Quiescent Current LDO Regulator, 8-Pin SOIC 150mil, Extended Temperature")
      (libsource (lib "Altium Content Vault") (part "PM-LINEREG-MCP1726-IL8A"))
    )
  )
  (nets
    (net (code "1") (name "/I2C_0_SCL_PM") (class "Default")
      (node (ref "P3") (pin "1") (pinfunction "1_1") (pintype "passive"))
      (node (ref "U2") (pin "9") (pinfunction "SCL_9") (pintype "input"))
      (node (ref "U4") (pin "9") (pinfunction "SCL_9") (pintype "input"))
      (node (ref "U6") (pin "9") (pinfunction "SCL_9") (pintype "input"))
    )
    (net (code "2") (name "/I2C_0_SDA_PM") (class "Default")
      (node (ref "P3") (pin "2") (pinfunction "2_2") (pintype "passive"))
      (node (ref "U2") (pin "10") (pinfunction "SDAI_10") (pintype "input"))
      (node (ref "U2") (pin "11") (pinfunction "SDAO_11") (pintype "output"))
      (node (ref "U4") (pin "10") (pinfunction "SDAI_10") (pintype "input"))
      (node (ref "U4") (pin "11") (pinfunction "SDAO_11") (pintype "output"))
      (node (ref "U6") (pin "10") (pinfunction "SDAI_10") (pintype "input"))
      (node (ref "U6") (pin "11") (pinfunction "SDAO_11") (pintype "output"))
    )
    (net (code "3") (name "/VDD_1V6_Shunt-") (class "Default")
      (node (ref "C26") (pin "2") (pinfunction "2_2") (pintype "passive"))
      (node (ref "C27") (pin "2") (pinfunction "2_2") (pintype "passive"))
      (node (ref "R17") (pin "1") (pinfunction "1_1") (pintype "passive"))
      (node (ref "U4") (pin "1") (pinfunction "SENSE1-_1") (pintype "passive"))
      (node (ref "U5") (pin "1") (pinfunction "VIN_1") (pintype "power_in"))
      (node (ref "U5") (pin "2") (pinfunction "VIN_2") (pintype "power_in"))
      (node (ref "U5") (pin "3") (pinfunction "~{SHDN}_3") (pintype "input"))
    )
    (net (code "4") (name "/VDD_1V8_Shunt-") (class "Default")
      (node (ref "C16") (pin "2") (pinfunction "2_2") (pintype "passive"))
      (node (ref "C17") (pin "2") (pinfunction "2_2") (pintype "passive"))
      (node (ref "R8") (pin "1") (pinfunction "1_1") (pintype "passive"))
      (node (ref "U2") (pin "16") (pinfunction "SENSE2-_16") (pintype "passive"))
      (node (ref "U3") (pin "1") (pinfunction "VIN_1") (pintype "power_in"))
      (node (ref "U3") (pin "2") (pinfunction "VIN_2") (pintype "power_in"))
      (node (ref "U3") (pin "3") (pinfunction "~{SHDN}_3") (pintype "input"))
    )
    (net (code "5") (name "/VDD_1V_D_Shunt-") (class "Default")
      (node (ref "C34") (pin "2") (pinfunction "2_2") (pintype "passive"))
      (node (ref "C35") (pin "2") (pinfunction "2_2") (pintype "passive"))
      (node (ref "R27") (pin "1") (pinfunction "1_1") (pintype "passive"))
      (node (ref "U6") (pin "1") (pinfunction "SENSE1-_1") (pintype "passive"))
      (node (ref "U7") (pin "1") (pinfunction "VIN_1") (pintype "power_in"))
      (node (ref "U7") (pin "2") (pinfunction "VIN_2") (pintype "power_in"))
      (node (ref "U7") (pin "3") (pinfunction "~{SHDN}_3") (pintype "input"))
    )
    (net (code "6") (name "/VDD_1V_On_Shunt-") (class "Default")
      (node (ref "C42") (pin "2") (pinfunction "2_2") (pintype "passive"))
      (node (ref "C43") (pin "2") (pinfunction "2_2") (pintype "passive"))
      (node (ref "R19") (pin "1") (pinfunction "1_1") (pintype "passive"))
      (node (ref "U4") (pin "16") (pinfunction "SENSE2-_16") (pintype "passive"))
      (node (ref "U8") (pin "1") (pinfunction "VIN_1") (pintype "power_in"))
      (node (ref "U8") (pin "2") (pinfunction "VIN_2") (pintype "power_in"))
      (node (ref "U8") (pin "3") (pinfunction "~{SHDN}_3") (pintype "input"))
    )
    (net (code "7") (name "/VDD_3V3_Shunt-") (class "Default")
      (node (ref "C3") (pin "2") (pinfunction "2_2") (pintype "passive"))
      (node (ref "C4") (pin "2") (pinfunction "2_2") (pintype "passive"))
      (node (ref "R5") (pin "1") (pinfunction "1_1") (pintype "passive"))
      (node (ref "U1") (pin "1") (pinfunction "VIN_1") (pintype "power_in"))
      (node (ref "U1") (pin "2") (pinfunction "VIN_2") (pintype "power_in"))
      (node (ref "U1") (pin "3") (pinfunction "~{SHDN}_3") (pintype "input"))
      (node (ref "U2") (pin "1") (pinfunction "SENSE1-_1") (pintype "passive"))
    )
    (net (code "8") (name "/VDD_V85_RF_Shunt-") (class "Default")
      (node (ref "C50") (pin "2") (pinfunction "2_2") (pintype "passive"))
      (node (ref "C51") (pin "2") (pinfunction "2_2") (pintype "passive"))
      (node (ref "R29") (pin "1") (pinfunction "1_1") (pintype "passive"))
      (node (ref "U6") (pin "16") (pinfunction "SENSE2-_16") (pintype "passive"))
      (node (ref "U9") (pin "1") (pinfunction "VIN_1") (pintype "power_in"))
      (node (ref "U9") (pin "2") (pinfunction "VIN_2") (pintype "power_in"))
      (node (ref "U9") (pin "3") (pinfunction "~{SHDN}_3") (pintype "input"))
    )
    (net (code "9") (name "1V8_DUT") (class "Default")
      (node (ref "C13") (pin "1") (pinfunction "1_1") (pintype "passive"))
      (node (ref "C14") (pin "1") (pinfunction "1_1") (pintype "passive"))
      (node (ref "C15") (pin "1") (pinfunction "1_1") (pintype "passive"))
      (node (ref "P4") (pin "2") (pinfunction "2_2") (pintype "passive"))
      (node (ref "R1") (pin "1") (pinfunction "1_1") (pintype "passive"))
    )
    (net (code "10") (name "1V8_IO") (class "Default")
      (node (ref "P12") (pin "2") (pinfunction "2_2") (pintype "passive"))
      (node (ref "R15") (pin "1") (pinfunction "1_1") (pintype "passive"))
    )
    (net (code "11") (name "3.3V_Reg") (class "Default")
      (node (ref "R2") (pin "1") (pinfunction "1_1") (pintype "passive"))
    )
    (net (code "12") (name "3V3") (class "Default")
      (node (ref "C12") (pin "2") (pinfunction "2_2") (pintype "passive"))
      (node (ref "C2") (pin "2") (pinfunction "2_2") (pintype "passive"))
      (node (ref "C22") (pin "2") (pinfunction "2_2") (pintype "passive"))
      (node (ref "P1") (pin "2") (pinfunction "2_2") (pintype "passive"))
      (node (ref "R11") (pin "1") (pinfunction "1_1") (pintype "passive"))
      (node (ref "R18") (pin "1") (pinfunction "1_1") (pintype "passive"))
      (node (ref "R21") (pin "1") (pinfunction "1_1") (pintype "passive"))
      (node (ref "R28") (pin "1") (pinfunction "1_1") (pintype "passive"))
      (node (ref "R3") (pin "1") (pinfunction "1_1") (pintype "passive"))
      (node (ref "R31") (pin "1") (pinfunction "1_1") (pintype "passive"))
      (node (ref "R33") (pin "1") (pinfunction "1_1") (pintype "passive"))
      (node (ref "R35") (pin "1") (pinfunction "1_1") (pintype "passive"))
      (node (ref "R37") (pin "1") (pinfunction "1_1") (pintype "passive"))
      (node (ref "R39") (pin "1") (pinfunction "1_1") (pintype "passive"))
      (node (ref "R41") (pin "1") (pinfunction "1_1") (pintype "passive"))
      (node (ref "R43") (pin "1") (pinfunction "1_1") (pintype "passive"))
      (node (ref "R45") (pin "1") (pinfunction "1_1") (pintype "passive"))
      (node (ref "R47") (pin "1") (pinfunction "1_1") (pintype "passive"))
      (node (ref "R7") (pin "1") (pinfunction "1_1") (pintype "passive"))
      (node (ref "U2") (pin "8") (pinfunction "VDD_8") (pintype "power_in"))
      (node (ref "U4") (pin "6") (pinfunction "ADR0_6") (pintype "input"))
      (node (ref "U4") (pin "8") (pinfunction "VDD_8") (pintype "power_in"))
      (node (ref "U6") (pin "5") (pinfunction "ADR1_5") (pintype "input"))
      (node (ref "U6") (pin "8") (pinfunction "VDD_8") (pintype "power_in"))
    )
    (net (code "13") (name "Ext_1V") (class "Default")
      (node (ref "J6") (pin "1") (pinfunction "1_1") (pintype "passive"))
      (node (ref "P6") (pin "3") (pinfunction "3_3") (pintype "passive"))
      (node (ref "P8") (pin "3") (pinfunction "3_3") (pintype "passive"))
    )
    (net (code "14") (name "Ext_1V6") (class "Default")
      (node (ref "J4") (pin "1") (pinfunction "1_1") (pintype "passive"))
      (node (ref "P5") (pin "3") (pinfunction "3_3") (pintype "passive"))
    )
    (net (code "15") (name "Ext_1V8") (class "Default")
      (node (ref "J3") (pin "1") (pinfunction "1_1") (pintype "passive"))
      (node (ref "P12") (pin "3") (pinfunction "3_3") (pintype "passive"))
      (node (ref "P4") (pin "3") (pinfunction "3_3") (pintype "passive"))
    )
    (net (code "16") (name "Ext_3V3") (class "Default")
      (node (ref "J2") (pin "1") (pinfunction "1_1") (pintype "passive"))
      (node (ref "P1") (pin "3") (pinfunction "3_3") (pintype "passive"))
    )
    (net (code "17") (name "Ext_V85") (class "Default")
      (node (ref "J7") (pin "1") (pinfunction "1_1") (pintype "passive"))
      (node (ref "P10") (pin "3") (pinfunction "3_3") (pintype "passive"))
    )
    (net (code "18") (name "Ext_VDD") (class "Default")
      (node (ref "C55") (pin "2") (pinfunction "2_2") (pintype "passive"))
      (node (ref "C56") (pin "2") (pinfunction "2_2") (pintype "passive"))
      (node (ref "C7") (pin "2") (pinfunction "2_2") (pintype "passive"))
      (node (ref "C8") (pin "2") (pinfunction "2_2") (pintype "passive"))
      (node (ref "C9") (pin "2") (pinfunction "2_2") (pintype "passive"))
      (node (ref "J1") (pin "1") (pinfunction "1_1") (pintype "passive"))
      (node (ref "P2") (pin "1") (pinfunction "1_1") (pintype "passive"))
      (node (ref "R17") (pin "2") (pinfunction "2_2") (pintype "passive"))
      (node (ref "R19") (pin "2") (pinfunction "2_2") (pintype "passive"))
      (node (ref "R27") (pin "2") (pinfunction "2_2") (pintype "passive"))
      (node (ref "R29") (pin "2") (pinfunction "2_2") (pintype "passive"))
      (node (ref "R5") (pin "2") (pinfunction "2_2") (pintype "passive"))
      (node (ref "R8") (pin "2") (pinfunction "2_2") (pintype "passive"))
      (node (ref "U10") (pin "1") (pinfunction "VIN_1") (pintype "power_in"))
      (node (ref "U10") (pin "2") (pinfunction "VIN_2") (pintype "power_in"))
      (node (ref "U10") (pin "3") (pinfunction "~{SHDN}_3") (pintype "input"))
      (node (ref "U2") (pin "15") (pinfunction "SENSE2+_15") (pintype "passive"))
      (node (ref "U2") (pin "2") (pinfunction "SENSE1+_2") (pintype "passive"))
      (node (ref "U4") (pin "15") (pinfunction "SENSE2+_15") (pintype "passive"))
      (node (ref "U4") (pin "2") (pinfunction "SENSE1+_2") (pintype "passive"))
      (node (ref "U6") (pin "15") (pinfunction "SENSE2+_15") (pintype "passive"))
      (node (ref "U6") (pin "2") (pinfunction "SENSE1+_2") (pintype "passive"))
    )
    (net (code "19") (name "FMC_3V3") (class "Default")
      (node (ref "P2") (pin "2") (pinfunction "2_2") (pintype "passive"))
    )
    (net (code "20") (name "GND") (class "Default")
      (node (ref "C1") (pin "2") (pinfunction "2_2") (pintype "passive"))
      (node (ref "C10") (pin "1") (pinfunction "1_1") (pintype "passive"))
      (node (ref "C11") (pin "2") (pinfunction "2_2") (pintype "passive"))
      (node (ref "C12") (pin "1") (pinfunction "1_1") (pintype "passive"))
      (node (ref "C13") (pin "2") (pinfunction "2_2") (pintype "passive"))
      (node (ref "C14") (pin "2") (pinfunction "2_2") (pintype "passive"))
      (node (ref "C15") (pin "2") (pinfunction "2_2") (pintype "passive"))
      (node (ref "C16") (pin "1") (pinfunction "1_1") (pintype "passive"))
      (node (ref "C17") (pin "1") (pinfunction "1_1") (pintype "passive"))
      (node (ref "C18") (pin "1") (pinfunction "1_1") (pintype "passive"))
      (node (ref "C19") (pin "1") (pinfunction "1_1") (pintype "passive"))
      (node (ref "C2") (pin "1") (pinfunction "1_1") (pintype "passive"))
      (node (ref "C20") (pin "1") (pinfunction "1_1") (pintype "passive"))
      (node (ref "C21") (pin "2") (pinfunction "2_2") (pintype "passive"))
      (node (ref "C22") (pin "1") (pinfunction "1_1") (pintype "passive"))
      (node (ref "C23") (pin "2") (pinfunction "2_2") (pintype "passive"))
      (node (ref "C24") (pin "2") (pinfunction "2_2") (pintype "passive"))
      (node (ref "C25") (pin "2") (pinfunction "2_2") (pintype "passive"))
      (node (ref "C26") (pin "1") (pinfunction "1_1") (pintype "passive"))
      (node (ref "C27") (pin "1") (pinfunction "1_1") (pintype "passive"))
      (node (ref "C28") (pin "1") (pinfunction "1_1") (pintype "passive"))
      (node (ref "C29") (pin "1") (pinfunction "1_1") (pintype "passive"))
      (node (ref "C3") (pin "1") (pinfunction "1_1") (pintype "passive"))
      (node (ref "C30") (pin "1") (pinfunction "1_1") (pintype "passive"))
      (node (ref "C31") (pin "2") (pinfunction "2_2") (pintype "passive"))
      (node (ref "C32") (pin "2") (pinfunction "2_2") (pintype "passive"))
      (node (ref "C33") (pin "2") (pinfunction "2_2") (pintype "passive"))
      (node (ref "C34") (pin "1") (pinfunction "1_1") (pintype "passive"))
      (node (ref "C35") (pin "1") (pinfunction "1_1") (pintype "passive"))
      (node (ref "C36") (pin "1") (pinfunction "1_1") (pintype "passive"))
      (node (ref "C37") (pin "1") (pinfunction "1_1") (pintype "passive"))
      (node (ref "C38") (pin "1") (pinfunction "1_1") (pintype "passive"))
      (node (ref "C39") (pin "2") (pinfunction "2_2") (pintype "passive"))
      (node (ref "C4") (pin "1") (pinfunction "1_1") (pintype "passive"))
      (node (ref "C40") (pin "2") (pinfunction "2_2") (pintype "passive"))
      (node (ref "C41") (pin "2") (pinfunction "2_2") (pintype "passive"))
      (node (ref "C42") (pin "1") (pinfunction "1_1") (pintype "passive"))
      (node (ref "C43") (pin "1") (pinfunction "1_1") (pintype "passive"))
      (node (ref "C44") (pin "1") (pinfunction "1_1") (pintype "passive"))
      (node (ref "C45") (pin "1") (pinfunction "1_1") (pintype "passive"))
      (node (ref "C46") (pin "1") (pinfunction "1_1") (pintype "passive"))
      (node (ref "C47") (pin "2") (pinfunction "2_2") (pintype "passive"))
      (node (ref "C48") (pin "2") (pinfunction "2_2") (pintype "passive"))
      (node (ref "C49") (pin "2") (pinfunction "2_2") (pintype "passive"))
      (node (ref "C5") (pin "1") (pinfunction "1_1") (pintype "passive"))
      (node (ref "C50") (pin "1") (pinfunction "1_1") (pintype "passive"))
      (node (ref "C51") (pin "1") (pinfunction "1_1") (pintype "passive"))
      (node (ref "C52") (pin "1") (pinfunction "1_1") (pintype "passive"))
      (node (ref "C53") (pin "1") (pinfunction "1_1") (pintype "passive"))
      (node (ref "C54") (pin "1") (pinfunction "1_1") (pintype "passive"))
      (node (ref "C55") (pin "1") (pinfunction "1_1") (pintype "passive"))
      (node (ref "C56") (pin "1") (pinfunction "1_1") (pintype "passive"))
      (node (ref "C57") (pin "1") (pinfunction "1_1") (pintype "passive"))
      (node (ref "C58") (pin "1") (pinfunction "1_1") (pintype "passive"))
      (node (ref "C59") (pin "1") (pinfunction "1_1") (pintype "passive"))
      (node (ref "C6") (pin "1") (pinfunction "1_1") (pintype "passive"))
      (node (ref "C7") (pin "1") (pinfunction "1_1") (pintype "passive"))
      (node (ref "C8") (pin "1") (pinfunction "1_1") (pintype "passive"))
      (node (ref "C9") (pin "1") (pinfunction "1_1") (pintype "passive"))
      (node (ref "J5") (pin "1") (pinfunction "1_1") (pintype "passive"))
      (node (ref "P3") (pin "3") (pinfunction "3_3") (pintype "passive"))
      (node (ref "Q1") (pin "3") (pinfunction "D_3") (pintype "passive"))
      (node (ref "Q2") (pin "3") (pinfunction "D_3") (pintype "passive"))
      (node (ref "Q3") (pin "3") (pinfunction "D_3") (pintype "passive"))
      (node (ref "Q4") (pin "3") (pinfunction "D_3") (pintype "passive"))
      (node (ref "Q5") (pin "3") (pinfunction "D_3") (pintype "passive"))
      (node (ref "Q6") (pin "3") (pinfunction "D_3") (pintype "passive"))
      (node (ref "Q7") (pin "3") (pinfunction "D_3") (pintype "passive"))
      (node (ref "R10") (pin "1") (pinfunction "1_1") (pintype "passive"))
      (node (ref "R20") (pin "1") (pinfunction "1_1") (pintype "passive"))
      (node (ref "R30") (pin "1") (pinfunction "1_1") (pintype "passive"))
      (node (ref "R34") (pin "1") (pinfunction "1_1") (pintype "passive"))
      (node (ref "R38") (pin "1") (pinfunction "1_1") (pintype "passive"))
      (node (ref "R42") (pin "1") (pinfunction "1_1") (pintype "passive"))
      (node (ref "R46") (pin "1") (pinfunction "1_1") (pintype "passive"))
      (node (ref "R6") (pin "2") (pinfunction "2_2") (pintype "passive"))
      (node (ref "R9") (pin "2") (pinfunction "2_2") (pintype "passive"))
      (node (ref "U1") (pin "4") (pinfunction "GND_4") (pintype "power_in"))
      (node (ref "U10") (pin "4") (pinfunction "GND_4") (pintype "power_in"))
      (node (ref "U2") (pin "12") (pinfunction "GND_12") (pintype "power_in"))
      (node (ref "U2") (pin "5") (pinfunction "ADR1_5") (pintype "input"))
      (node (ref "U2") (pin "6") (pinfunction "ADR0_6") (pintype "input"))
      (node (ref "U3") (pin "4") (pinfunction "GND_4") (pintype "power_in"))
      (node (ref "U4") (pin "12") (pinfunction "GND_12") (pintype "power_in"))
      (node (ref "U4") (pin "5") (pinfunction "ADR1_5") (pintype "input"))
      (node (ref "U5") (pin "4") (pinfunction "GND_4") (pintype "power_in"))
      (node (ref "U6") (pin "12") (pinfunction "GND_12") (pintype "power_in"))
      (node (ref "U6") (pin "6") (pinfunction "ADR0_6") (pintype "input"))
      (node (ref "U7") (pin "4") (pinfunction "GND_4") (pintype "power_in"))
      (node (ref "U8") (pin "4") (pinfunction "GND_4") (pintype "power_in"))
      (node (ref "U9") (pin "4") (pinfunction "GND_4") (pintype "power_in"))
    )
    (net (code "21") (name "LDO_VDD_ALWAYS_ON") (class "Default")
      (node (ref "P9") (pin "2") (pinfunction "2_2") (pintype "passive"))
      (node (ref "R13") (pin "1") (pinfunction "1_1") (pintype "passive"))
    )
    (net (code "22") (name "LDO_VDD_A_RF") (class "Default")
      (node (ref "P11") (pin "2") (pinfunction "2_2") (pintype "passive"))
      (node (ref "R25") (pin "1") (pinfunction "1_1") (pintype "passive"))
    )
    (net (code "23") (name "LDO_VDD_D") (class "Default")
      (node (ref "P7") (pin "2") (pinfunction "2_2") (pintype "passive"))
      (node (ref "R22") (pin "1") (pinfunction "1_1") (pintype "passive"))
    )
    (net (code "24") (name "Net-(D1-PadA)") (class "Default")
      (node (ref "D1") (pin "A") (pinfunction "A_A") (pintype "passive"))
      (node (ref "R11") (pin "2") (pinfunction "2_2") (pintype "passive"))
    )
    (net (code "25") (name "Net-(D2-PadA)") (class "Default")
      (node (ref "D2") (pin "A") (pinfunction "A_A") (pintype "passive"))
      (node (ref "R21") (pin "2") (pinfunction "2_2") (pintype "passive"))
    )
    (net (code "26") (name "Net-(D3-PadA)") (class "Default")
      (node (ref "D3") (pin "A") (pinfunction "A_A") (pintype "passive"))
      (node (ref "R31") (pin "2") (pinfunction "2_2") (pintype "passive"))
    )
    (net (code "27") (name "Net-(D4-PadA)") (class "Default")
      (node (ref "D4") (pin "A") (pinfunction "A_A") (pintype "passive"))
      (node (ref "R35") (pin "2") (pinfunction "2_2") (pintype "passive"))
    )
    (net (code "28") (name "Net-(D5-PadA)") (class "Default")
      (node (ref "D5") (pin "A") (pinfunction "A_A") (pintype "passive"))
      (node (ref "R39") (pin "2") (pinfunction "2_2") (pintype "passive"))
    )
    (net (code "29") (name "Net-(D6-PadA)") (class "Default")
      (node (ref "D6") (pin "A") (pinfunction "A_A") (pintype "passive"))
      (node (ref "R43") (pin "2") (pinfunction "2_2") (pintype "passive"))
    )
    (net (code "30") (name "Net-(D7-PadA)") (class "Default")
      (node (ref "D7") (pin "A") (pinfunction "A_A") (pintype "passive"))
      (node (ref "R47") (pin "2") (pinfunction "2_2") (pintype "passive"))
    )
    (net (code "31") (name "Net-(Q1-G)") (class "Default")
      (node (ref "Q1") (pin "1") (pinfunction "G_1") (pintype "passive"))
      (node (ref "R7") (pin "2") (pinfunction "2_2") (pintype "passive"))
      (node (ref "U1") (pin "5") (pinfunction "PWRGD_5") (pintype "power_in"))
    )
    (net (code "32") (name "Net-(Q1-S)") (class "Default")
      (node (ref "D1") (pin "C") (pinfunction "C_C") (pintype "passive"))
      (node (ref "Q1") (pin "2") (pinfunction "S_2") (pintype "passive"))
    )
    (net (code "33") (name "Net-(Q2-G)") (class "Default")
      (node (ref "Q2") (pin "1") (pinfunction "G_1") (pintype "passive"))
      (node (ref "R18") (pin "2") (pinfunction "2_2") (pintype "passive"))
      (node (ref "U3") (pin "5") (pinfunction "PWRGD_5") (pintype "power_in"))
    )
    (net (code "34") (name "Net-(Q2-S)") (class "Default")
      (node (ref "D2") (pin "C") (pinfunction "C_C") (pintype "passive"))
      (node (ref "Q2") (pin "2") (pinfunction "S_2") (pintype "passive"))
    )
    (net (code "35") (name "Net-(Q3-G)") (class "Default")
      (node (ref "Q3") (pin "1") (pinfunction "G_1") (pintype "passive"))
      (node (ref "R28") (pin "2") (pinfunction "2_2") (pintype "passive"))
      (node (ref "U5") (pin "5") (pinfunction "PWRGD_5") (pintype "power_in"))
    )
    (net (code "36") (name "Net-(Q3-S)") (class "Default")
      (node (ref "D3") (pin "C") (pinfunction "C_C") (pintype "passive"))
      (node (ref "Q3") (pin "2") (pinfunction "S_2") (pintype "passive"))
    )
    (net (code "37") (name "Net-(Q4-G)") (class "Default")
      (node (ref "Q4") (pin "1") (pinfunction "G_1") (pintype "passive"))
      (node (ref "R33") (pin "2") (pinfunction "2_2") (pintype "passive"))
      (node (ref "U7") (pin "5") (pinfunction "PWRGD_5") (pintype "power_in"))
    )
    (net (code "38") (name "Net-(Q4-S)") (class "Default")
      (node (ref "D4") (pin "C") (pinfunction "C_C") (pintype "passive"))
      (node (ref "Q4") (pin "2") (pinfunction "S_2") (pintype "passive"))
    )
    (net (code "39") (name "Net-(Q5-G)") (class "Default")
      (node (ref "Q5") (pin "1") (pinfunction "G_1") (pintype "passive"))
      (node (ref "R37") (pin "2") (pinfunction "2_2") (pintype "passive"))
      (node (ref "U8") (pin "5") (pinfunction "PWRGD_5") (pintype "power_in"))
    )
    (net (code "40") (name "Net-(Q6-G)") (class "Default")
      (node (ref "Q6") (pin "1") (pinfunction "G_1") (pintype "passive"))
      (node (ref "R41") (pin "2") (pinfunction "2_2") (pintype "passive"))
      (node (ref "U9") (pin "5") (pinfunction "PWRGD_5") (pintype "power_in"))
    )
    (net (code "41") (name "Net-(Q6-S)") (class "Default")
      (node (ref "D6") (pin "C") (pinfunction "C_C") (pintype "passive"))
      (node (ref "Q6") (pin "2") (pinfunction "S_2") (pintype "passive"))
    )
    (net (code "42") (name "Net-(Q7-G)") (class "Default")
      (node (ref "Q7") (pin "1") (pinfunction "G_1") (pintype "passive"))
      (node (ref "R45") (pin "2") (pinfunction "2_2") (pintype "passive"))
      (node (ref "U10") (pin "5") (pinfunction "PWRGD_5") (pintype "power_in"))
    )
    (net (code "43") (name "Net-(Q7-S)") (class "Default")
      (node (ref "D7") (pin "C") (pinfunction "C_C") (pintype "passive"))
      (node (ref "Q7") (pin "2") (pinfunction "S_2") (pintype "passive"))
    )
    (net (code "44") (name "Net-(U1-ADJ)") (class "Default")
      (node (ref "R10") (pin "2") (pinfunction "2_2") (pintype "passive"))
      (node (ref "R4") (pin "1") (pinfunction "1_1") (pintype "passive"))
      (node (ref "U1") (pin "7") (pinfunction "ADJ_7") (pintype "input"))
    )
    (net (code "45") (name "Net-(U1-CDELAY)") (class "Default")
      (node (ref "C10") (pin "2") (pinfunction "2_2") (pintype "passive"))
      (node (ref "U1") (pin "6") (pinfunction "CDELAY_6") (pintype "passive"))
    )
    (net (code "46") (name "Net-(U2-GPIO2)") (class "Default")
      (node (ref "R1") (pin "2") (pinfunction "2_2") (pintype "passive"))
      (node (ref "U2") (pin "14") (pinfunction "GPIO2_14") (pintype "bidirectional"))
    )
    (net (code "47") (name "Net-(U2-GPIO3)") (class "Default")
      (node (ref "R2") (pin "2") (pinfunction "2_2") (pintype "passive"))
      (node (ref "R6") (pin "1") (pinfunction "1_1") (pintype "passive"))
      (node (ref "U2") (pin "4") (pinfunction "GPIO3_4") (pintype "bidirectional"))
    )
    (net (code "48") (name "Net-(U2-GPIO4)") (class "Default")
      (node (ref "R3") (pin "2") (pinfunction "2_2") (pintype "passive"))
      (node (ref "R9") (pin "1") (pinfunction "1_1") (pintype "passive"))
      (node (ref "U2") (pin "13") (pinfunction "GPIO4_13") (pintype "bidirectional"))
    )
    (net (code "49") (name "Net-(U2-INTVCC)") (class "Default")
      (node (ref "C1") (pin "1") (pinfunction "1_1") (pintype "passive"))
      (node (ref "U2") (pin "7") (pinfunction "INTVCC_7") (pintype "power_in"))
    )
    (net (code "50") (name "Net-(U3-ADJ)") (class "Default")
      (node (ref "R16") (pin "1") (pinfunction "1_1") (pintype "passive"))
      (node (ref "R20") (pin "2") (pinfunction "2_2") (pintype "passive"))
      (node (ref "U3") (pin "7") (pinfunction "ADJ_7") (pintype "input"))
    )
    (net (code "51") (name "Net-(U3-CDELAY)") (class "Default")
      (node (ref "C20") (pin "2") (pinfunction "2_2") (pintype "passive"))
      (node (ref "U3") (pin "6") (pinfunction "CDELAY_6") (pintype "passive"))
    )
    (net (code "52") (name "Net-(U4-GPIO1)") (class "Default")
      (node (ref "R12") (pin "2") (pinfunction "2_2") (pintype "passive"))
      (node (ref "U4") (pin "3") (pinfunction "GPIO1_3") (pintype "bidirectional"))
    )
    (net (code "53") (name "Net-(U4-GPIO2)") (class "Default")
      (node (ref "R13") (pin "2") (pinfunction "2_2") (pintype "passive"))
      (node (ref "U4") (pin "14") (pinfunction "GPIO2_14") (pintype "bidirectional"))
    )
    (net (code "54") (name "Net-(U4-GPIO3)") (class "Default")
      (node (ref "R14") (pin "2") (pinfunction "2_2") (pintype "passive"))
      (node (ref "U4") (pin "4") (pinfunction "GPIO3_4") (pintype "bidirectional"))
    )
    (net (code "55") (name "Net-(U4-GPIO4)") (class "Default")
      (node (ref "R15") (pin "2") (pinfunction "2_2") (pintype "passive"))
      (node (ref "U4") (pin "13") (pinfunction "GPIO4_13") (pintype "bidirectional"))
    )
    (net (code "56") (name "Net-(U4-INTVCC)") (class "Default")
      (node (ref "C11") (pin "1") (pinfunction "1_1") (pintype "passive"))
      (node (ref "U4") (pin "7") (pinfunction "INTVCC_7") (pintype "power_in"))
    )
    (net (code "57") (name "Net-(U5-ADJ)") (class "Default")
      (node (ref "R26") (pin "1") (pinfunction "1_1") (pintype "passive"))
      (node (ref "R30") (pin "2") (pinfunction "2_2") (pintype "passive"))
      (node (ref "U5") (pin "7") (pinfunction "ADJ_7") (pintype "input"))
    )
    (net (code "58") (name "Net-(U5-CDELAY)") (class "Default")
      (node (ref "C30") (pin "2") (pinfunction "2_2") (pintype "passive"))
      (node (ref "U5") (pin "6") (pinfunction "CDELAY_6") (pintype "passive"))
    )
    (net (code "59") (name "Net-(U6-GPIO1)") (class "Default")
      (node (ref "R22") (pin "2") (pinfunction "2_2") (pintype "passive"))
      (node (ref "U6") (pin "3") (pinfunction "GPIO1_3") (pintype "bidirectional"))
    )
    (net (code "60") (name "Net-(U6-GPIO2)") (class "Default")
      (node (ref "R23") (pin "2") (pinfunction "2_2") (pintype "passive"))
      (node (ref "U6") (pin "14") (pinfunction "GPIO2_14") (pintype "bidirectional"))
    )
    (net (code "61") (name "Net-(U6-GPIO3)") (class "Default")
      (node (ref "R24") (pin "2") (pinfunction "2_2") (pintype "passive"))
      (node (ref "U6") (pin "4") (pinfunction "GPIO3_4") (pintype "bidirectional"))
    )
    (net (code "62") (name "Net-(U6-GPIO4)") (class "Default")
      (node (ref "R25") (pin "2") (pinfunction "2_2") (pintype "passive"))
      (node (ref "U6") (pin "13") (pinfunction "GPIO4_13") (pintype "bidirectional"))
    )
    (net (code "63") (name "Net-(U6-INTVCC)") (class "Default")
      (node (ref "C21") (pin "1") (pinfunction "1_1") (pintype "passive"))
      (node (ref "U6") (pin "7") (pinfunction "INTVCC_7") (pintype "power_in"))
    )
    (net (code "64") (name "Net-(U7-ADJ)") (class "Default")
      (node (ref "R32") (pin "1") (pinfunction "1_1") (pintype "passive"))
      (node (ref "R34") (pin "2") (pinfunction "2_2") (pintype "passive"))
      (node (ref "U7") (pin "7") (pinfunction "ADJ_7") (pintype "input"))
    )
    (net (code "65") (name "Net-(U7-CDELAY)") (class "Default")
      (node (ref "C38") (pin "2") (pinfunction "2_2") (pintype "passive"))
      (node (ref "U7") (pin "6") (pinfunction "CDELAY_6") (pintype "passive"))
    )
    (net (code "66") (name "Net-(U8-ADJ)") (class "Default")
      (node (ref "R36") (pin "1") (pinfunction "1_1") (pintype "passive"))
      (node (ref "R38") (pin "2") (pinfunction "2_2") (pintype "passive"))
      (node (ref "U8") (pin "7") (pinfunction "ADJ_7") (pintype "input"))
    )
    (net (code "67") (name "Net-(U8-CDELAY)") (class "Default")
      (node (ref "C46") (pin "2") (pinfunction "2_2") (pintype "passive"))
      (node (ref "U8") (pin "6") (pinfunction "CDELAY_6") (pintype "passive"))
    )
    (net (code "68") (name "Net-(U9-ADJ)") (class "Default")
      (node (ref "R40") (pin "1") (pinfunction "1_1") (pintype "passive"))
      (node (ref "R42") (pin "2") (pinfunction "2_2") (pintype "passive"))
      (node (ref "U9") (pin "7") (pinfunction "ADJ_7") (pintype "input"))
    )
    (net (code "69") (name "Net-(U9-CDELAY)") (class "Default")
      (node (ref "C54") (pin "2") (pinfunction "2_2") (pintype "passive"))
      (node (ref "U9") (pin "6") (pinfunction "CDELAY_6") (pintype "passive"))
    )
    (net (code "70") (name "Net-(U10-ADJ)") (class "Default")
      (node (ref "R44") (pin "1") (pinfunction "1_1") (pintype "passive"))
      (node (ref "R46") (pin "2") (pinfunction "2_2") (pintype "passive"))
      (node (ref "U10") (pin "7") (pinfunction "ADJ_7") (pintype "input"))
    )
    (net (code "71") (name "Net-(U10-CDELAY)") (class "Default")
      (node (ref "C59") (pin "2") (pinfunction "2_2") (pintype "passive"))
      (node (ref "U10") (pin "6") (pinfunction "CDELAY_6") (pintype "passive"))
    )
    (net (code "72") (name "Reg_1V6") (class "Default")
      (node (ref "C28") (pin "2") (pinfunction "2_2") (pintype "passive"))
      (node (ref "C29") (pin "2") (pinfunction "2_2") (pintype "passive"))
      (node (ref "P5") (pin "1") (pinfunction "1_1") (pintype "passive"))
      (node (ref "R26") (pin "2") (pinfunction "2_2") (pintype "passive"))
      (node (ref "U5") (pin "8") (pinfunction "VOUT_8") (pintype "power_in"))
    )
    (net (code "73") (name "Reg_1V8") (class "Default")
      (node (ref "C18") (pin "2") (pinfunction "2_2") (pintype "passive"))
      (node (ref "C19") (pin "2") (pinfunction "2_2") (pintype "passive"))
      (node (ref "P4") (pin "1") (pinfunction "1_1") (pintype "passive"))
      (node (ref "R16") (pin "2") (pinfunction "2_2") (pintype "passive"))
      (node (ref "U3") (pin "8") (pinfunction "VOUT_8") (pintype "power_in"))
    )
    (net (code "74") (name "Reg_1V8_IO") (class "Default")
      (node (ref "C57") (pin "2") (pinfunction "2_2") (pintype "passive"))
      (node (ref "C58") (pin "2") (pinfunction "2_2") (pintype "passive"))
      (node (ref "P12") (pin "1") (pinfunction "1_1") (pintype "passive"))
      (node (ref "R44") (pin "2") (pinfunction "2_2") (pintype "passive"))
      (node (ref "U10") (pin "8") (pinfunction "VOUT_8") (pintype "power_in"))
    )
    (net (code "75") (name "Reg_1V_D") (class "Default")
      (node (ref "C36") (pin "2") (pinfunction "2_2") (pintype "passive"))
      (node (ref "C37") (pin "2") (pinfunction "2_2") (pintype "passive"))
      (node (ref "P6") (pin "1") (pinfunction "1_1") (pintype "passive"))
      (node (ref "R32") (pin "2") (pinfunction "2_2") (pintype "passive"))
      (node (ref "U7") (pin "8") (pinfunction "VOUT_8") (pintype "power_in"))
    )
    (net (code "76") (name "Reg_1V_On") (class "Default")
      (node (ref "C44") (pin "2") (pinfunction "2_2") (pintype "passive"))
      (node (ref "C45") (pin "2") (pinfunction "2_2") (pintype "passive"))
      (node (ref "P8") (pin "1") (pinfunction "1_1") (pintype "passive"))
      (node (ref "R36") (pin "2") (pinfunction "2_2") (pintype "passive"))
      (node (ref "U8") (pin "8") (pinfunction "VOUT_8") (pintype "power_in"))
    )
    (net (code "77") (name "Reg_3V3") (class "Default")
      (node (ref "C5") (pin "2") (pinfunction "2_2") (pintype "passive"))
      (node (ref "C6") (pin "2") (pinfunction "2_2") (pintype "passive"))
      (node (ref "P1") (pin "1") (pinfunction "1_1") (pintype "passive"))
      (node (ref "R4") (pin "2") (pinfunction "2_2") (pintype "passive"))
      (node (ref "U1") (pin "8") (pinfunction "VOUT_8") (pintype "power_in"))
    )
    (net (code "78") (name "Reg_V85_RF") (class "Default")
      (node (ref "C52") (pin "2") (pinfunction "2_2") (pintype "passive"))
      (node (ref "C53") (pin "2") (pinfunction "2_2") (pintype "passive"))
      (node (ref "P10") (pin "1") (pinfunction "1_1") (pintype "passive"))
      (node (ref "R40") (pin "2") (pinfunction "2_2") (pintype "passive"))
      (node (ref "U9") (pin "8") (pinfunction "VOUT_8") (pintype "power_in"))
    )
    (net (code "79") (name "VDD_ALWAYS_ON") (class "Default")
      (node (ref "C39") (pin "1") (pinfunction "1_1") (pintype "passive"))
      (node (ref "C40") (pin "1") (pinfunction "1_1") (pintype "passive"))
      (node (ref "C41") (pin "1") (pinfunction "1_1") (pintype "passive"))
      (node (ref "P8") (pin "2") (pinfunction "2_2") (pintype "passive"))
      (node (ref "P9") (pin "1") (pinfunction "1_1") (pintype "passive"))
      (node (ref "R14") (pin "1") (pinfunction "1_1") (pintype "passive"))
    )
    (net (code "80") (name "VDD_A_RF") (class "Default")
      (node (ref "C47") (pin "1") (pinfunction "1_1") (pintype "passive"))
      (node (ref "C48") (pin "1") (pinfunction "1_1") (pintype "passive"))
      (node (ref "C49") (pin "1") (pinfunction "1_1") (pintype "passive"))
      (node (ref "P10") (pin "2") (pinfunction "2_2") (pintype "passive"))
      (node (ref "P11") (pin "1") (pinfunction "1_1") (pintype "passive"))
      (node (ref "R24") (pin "1") (pinfunction "1_1") (pintype "passive"))
    )
    (net (code "81") (name "VDD_BATT") (class "Default")
      (node (ref "C23") (pin "1") (pinfunction "1_1") (pintype "passive"))
      (node (ref "C24") (pin "1") (pinfunction "1_1") (pintype "passive"))
      (node (ref "C25") (pin "1") (pinfunction "1_1") (pintype "passive"))
      (node (ref "P5") (pin "2") (pinfunction "2_2") (pintype "passive"))
      (node (ref "R12") (pin "1") (pinfunction "1_1") (pintype "passive"))
    )
    (net (code "82") (name "VDD_D") (class "Default")
      (node (ref "C31") (pin "1") (pinfunction "1_1") (pintype "passive"))
      (node (ref "C32") (pin "1") (pinfunction "1_1") (pintype "passive"))
      (node (ref "C33") (pin "1") (pinfunction "1_1") (pintype "passive"))
      (node (ref "P6") (pin "2") (pinfunction "2_2") (pintype "passive"))
      (node (ref "P7") (pin "1") (pinfunction "1_1") (pintype "passive"))
      (node (ref "R23") (pin "1") (pinfunction "1_1") (pintype "passive"))
    )
    (net (code "83") (name "unconnected-(D5-PadC)") (class "Default")
      (node (ref "D5") (pin "C") (pinfunction "C_C") (pintype "passive"))
    )
    (net (code "84") (name "unconnected-(Q5-S-Pad2)") (class "Default")
      (node (ref "Q5") (pin "2") (pinfunction "S_2") (pintype "passive"))
    )
    (net (code "85") (name "unconnected-(U2-GPIO1-Pad3)") (class "Default")
      (node (ref "U2") (pin "3") (pinfunction "GPIO1_3") (pintype "bidirectional+no_connect"))
    )
  )
)
